# SensorNodeBoard_4_2_1AZ1b.net
KiCad netlist of a schematic drawn in EAGLE
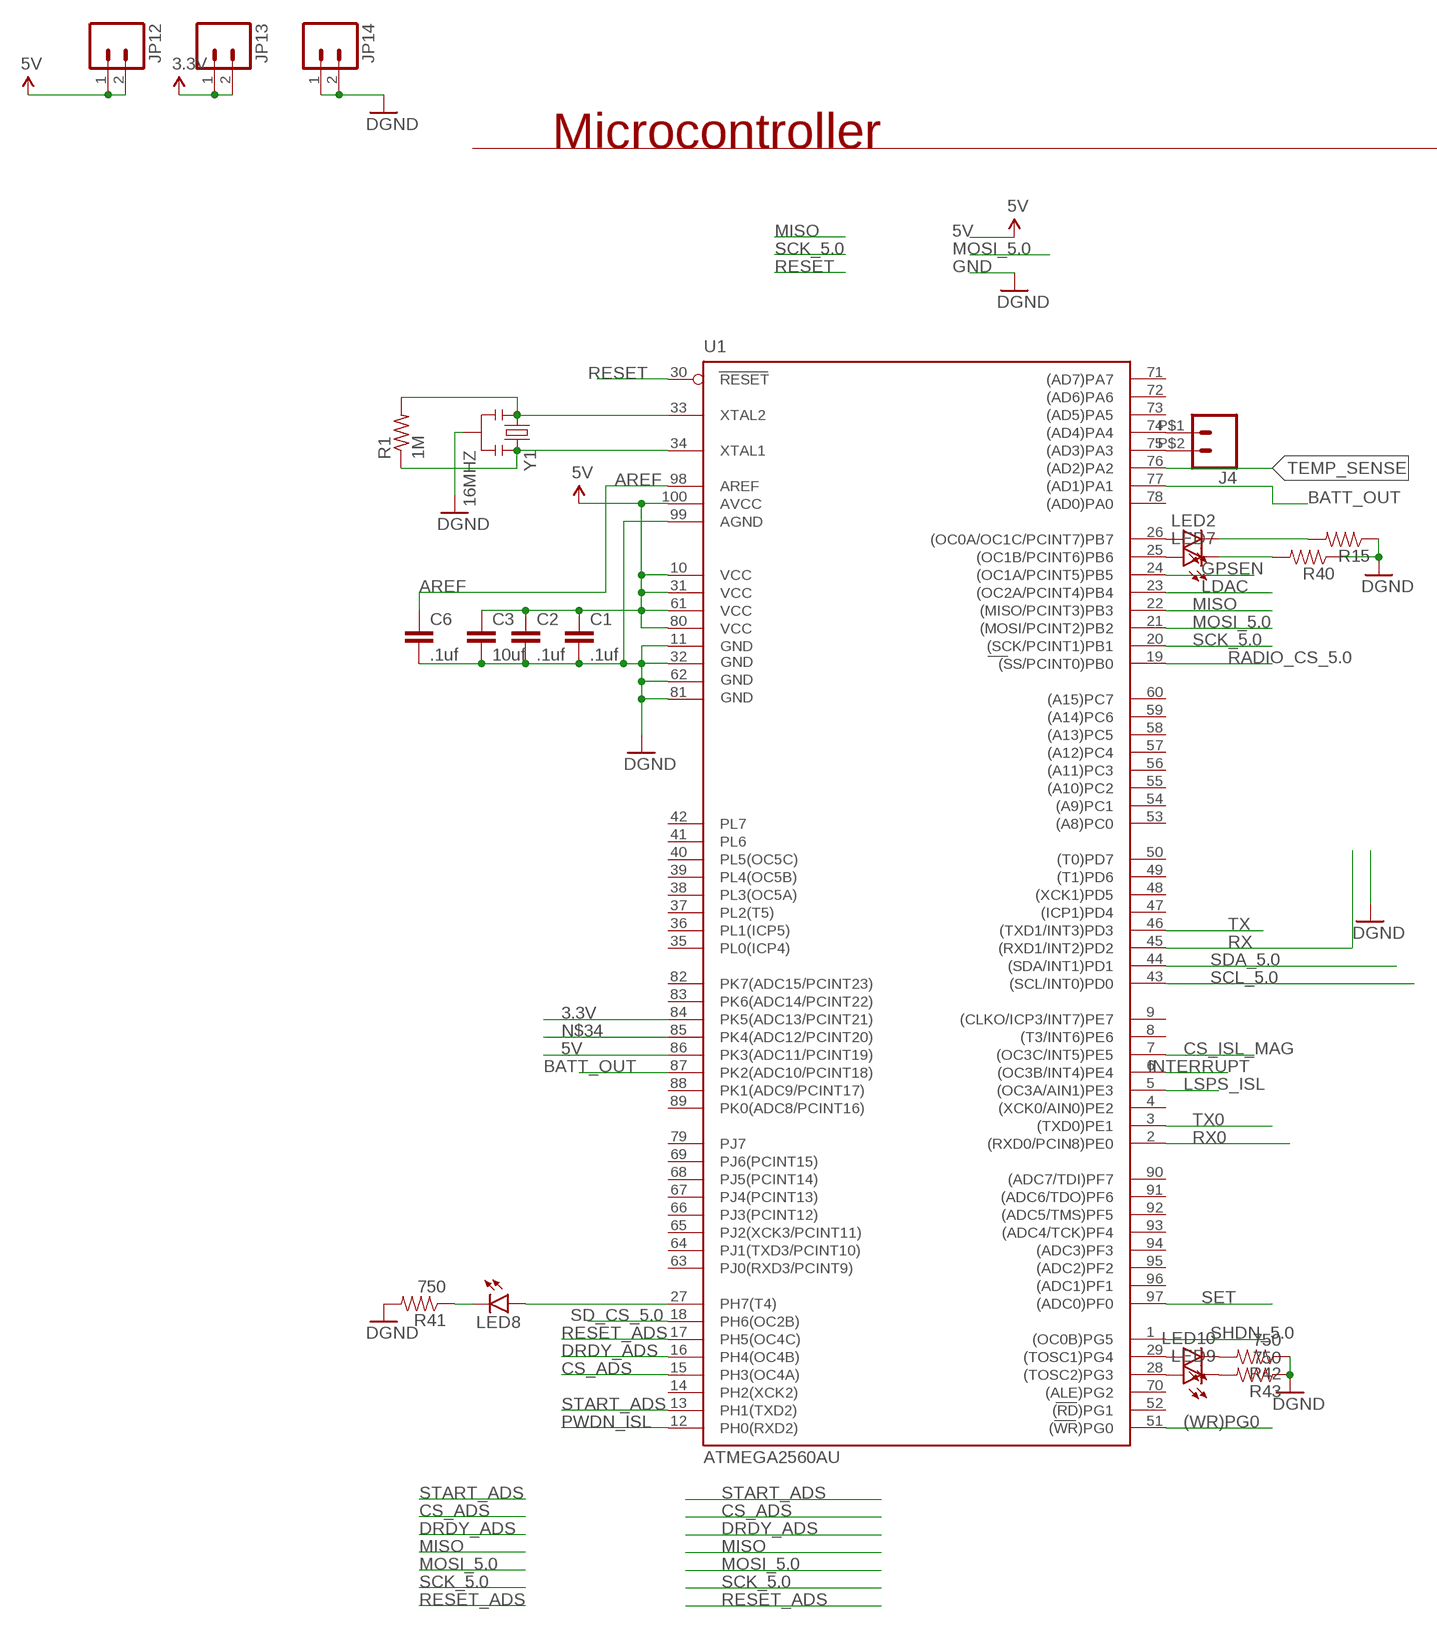
[diagram p0: schematic, sheet 1, part 1 of 2]
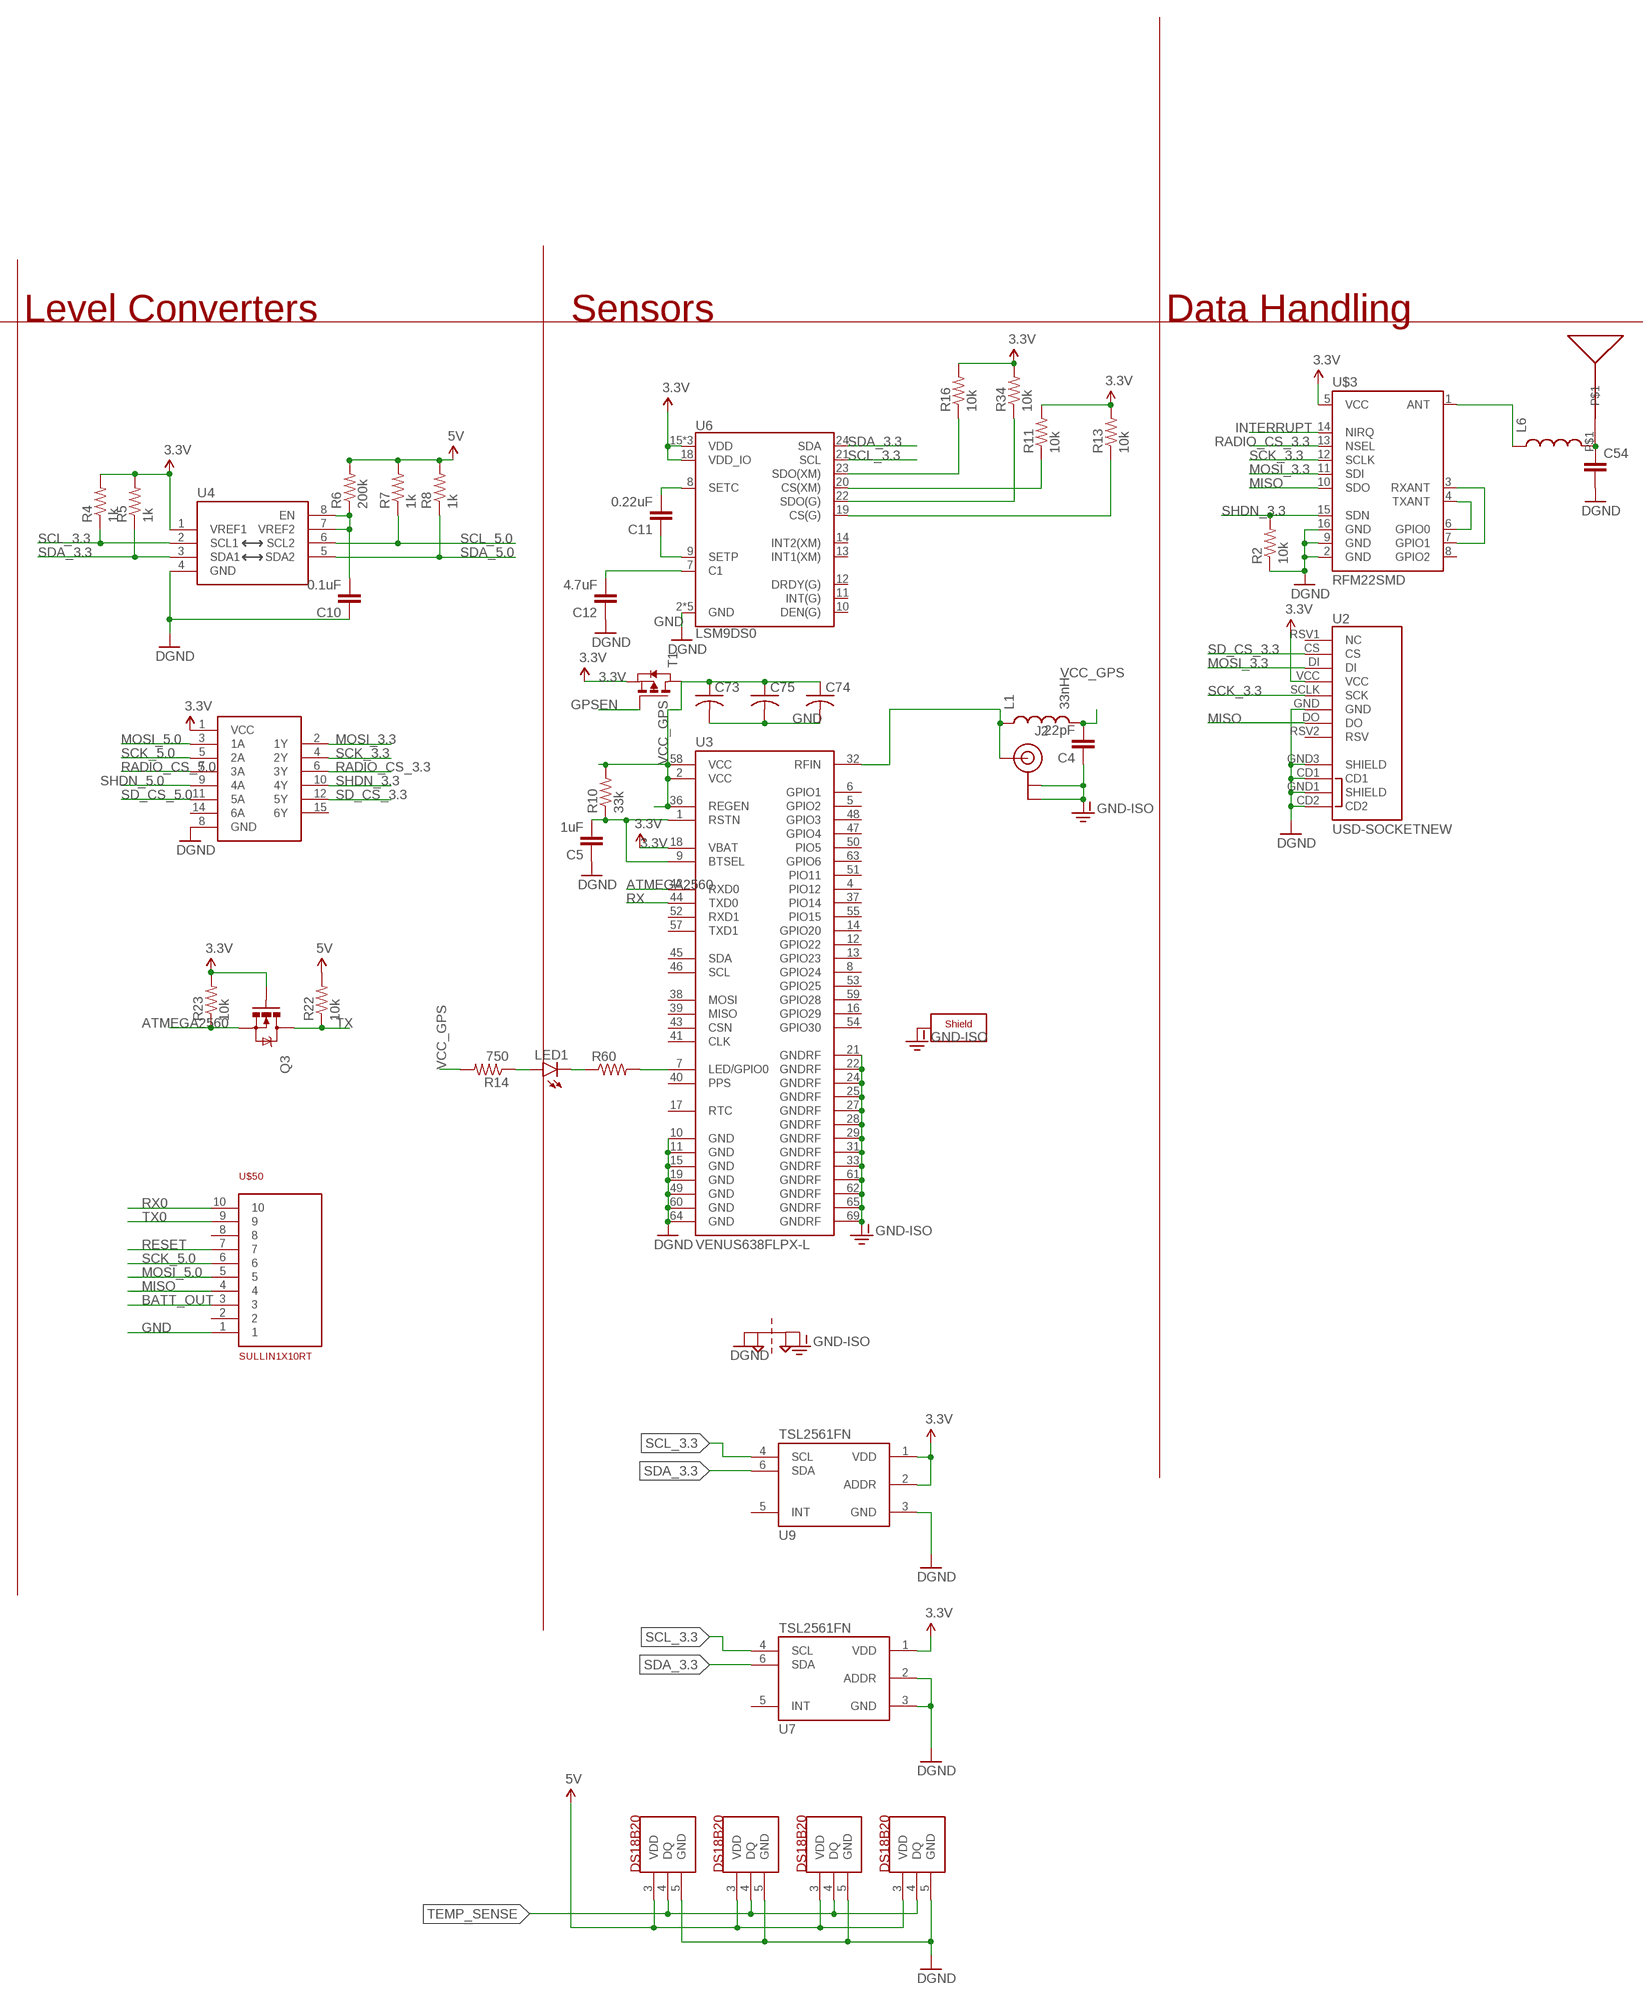
[diagram p1: schematic, sheet 1, part 2 of 2]
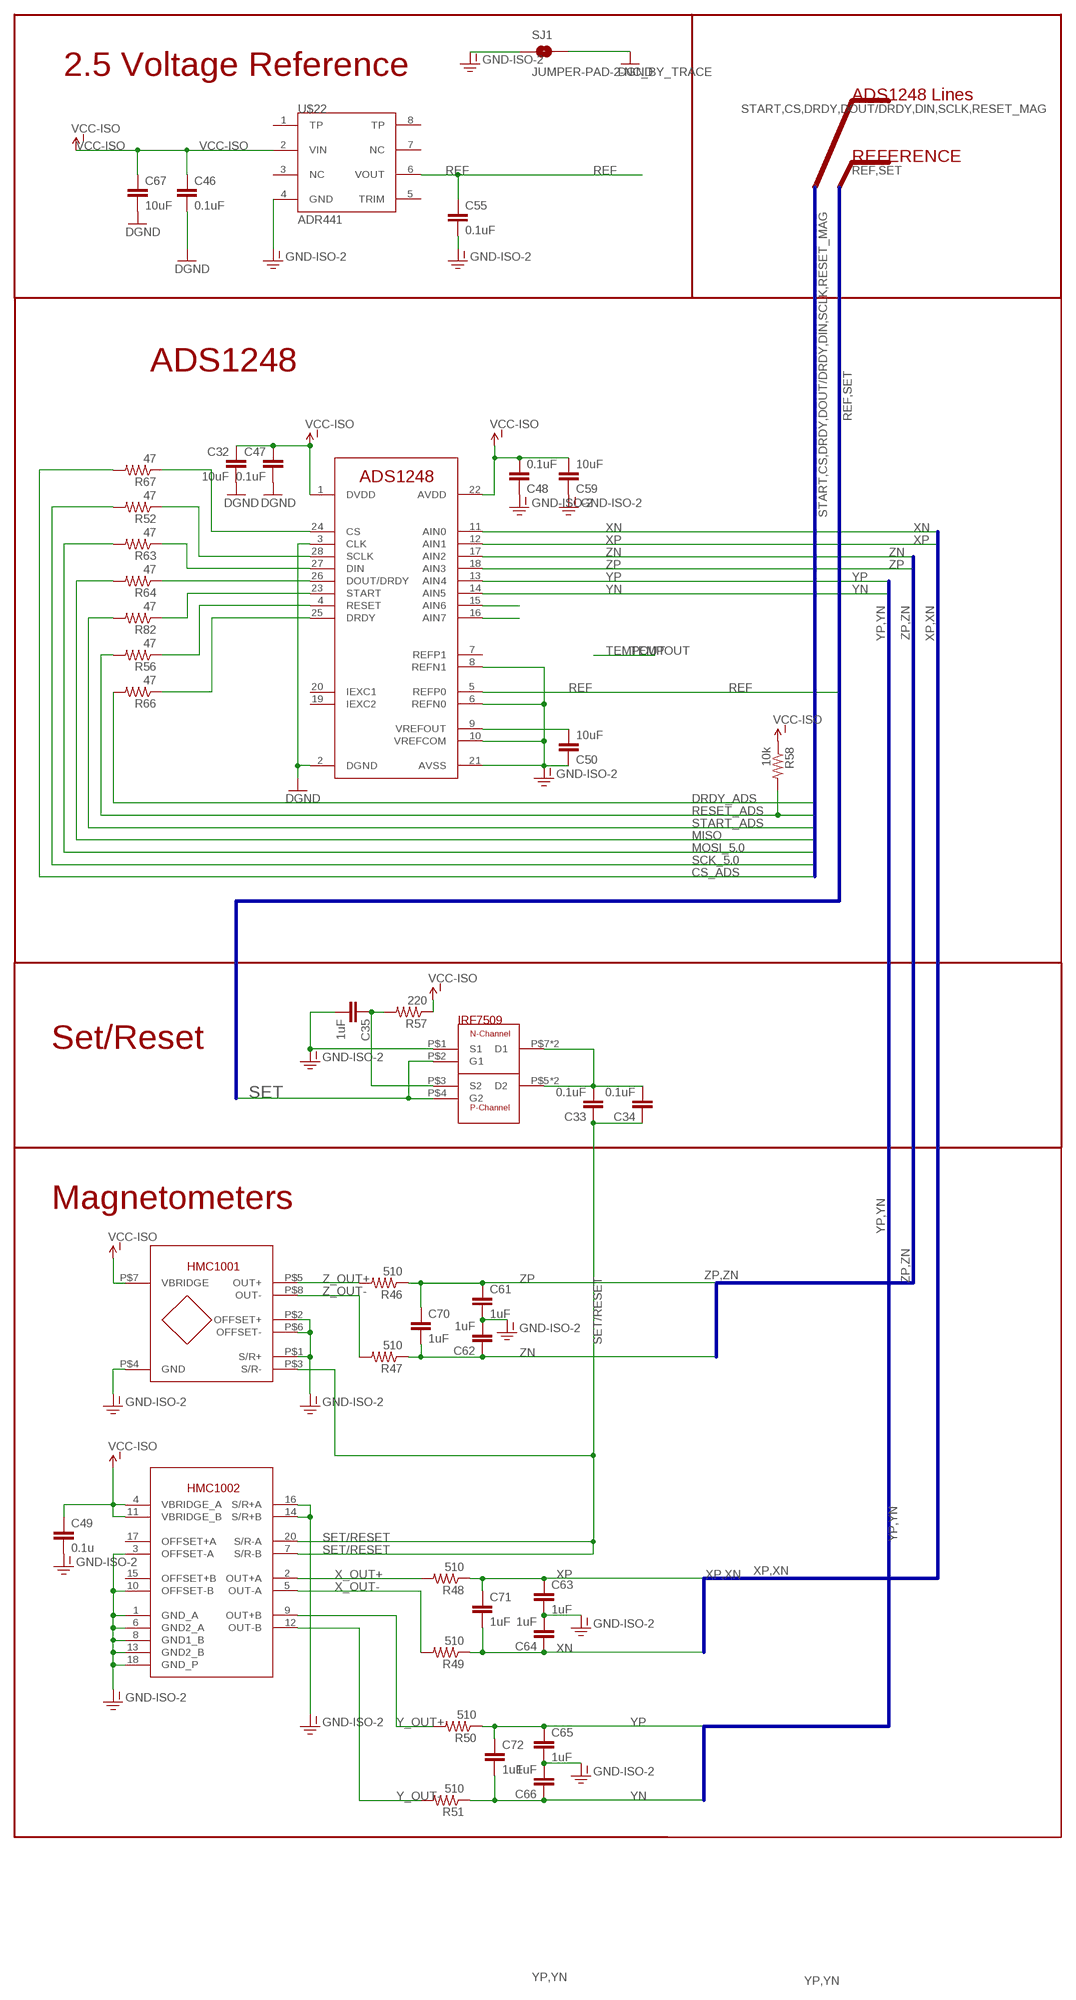
[diagram p2: schematic, sheet 2]
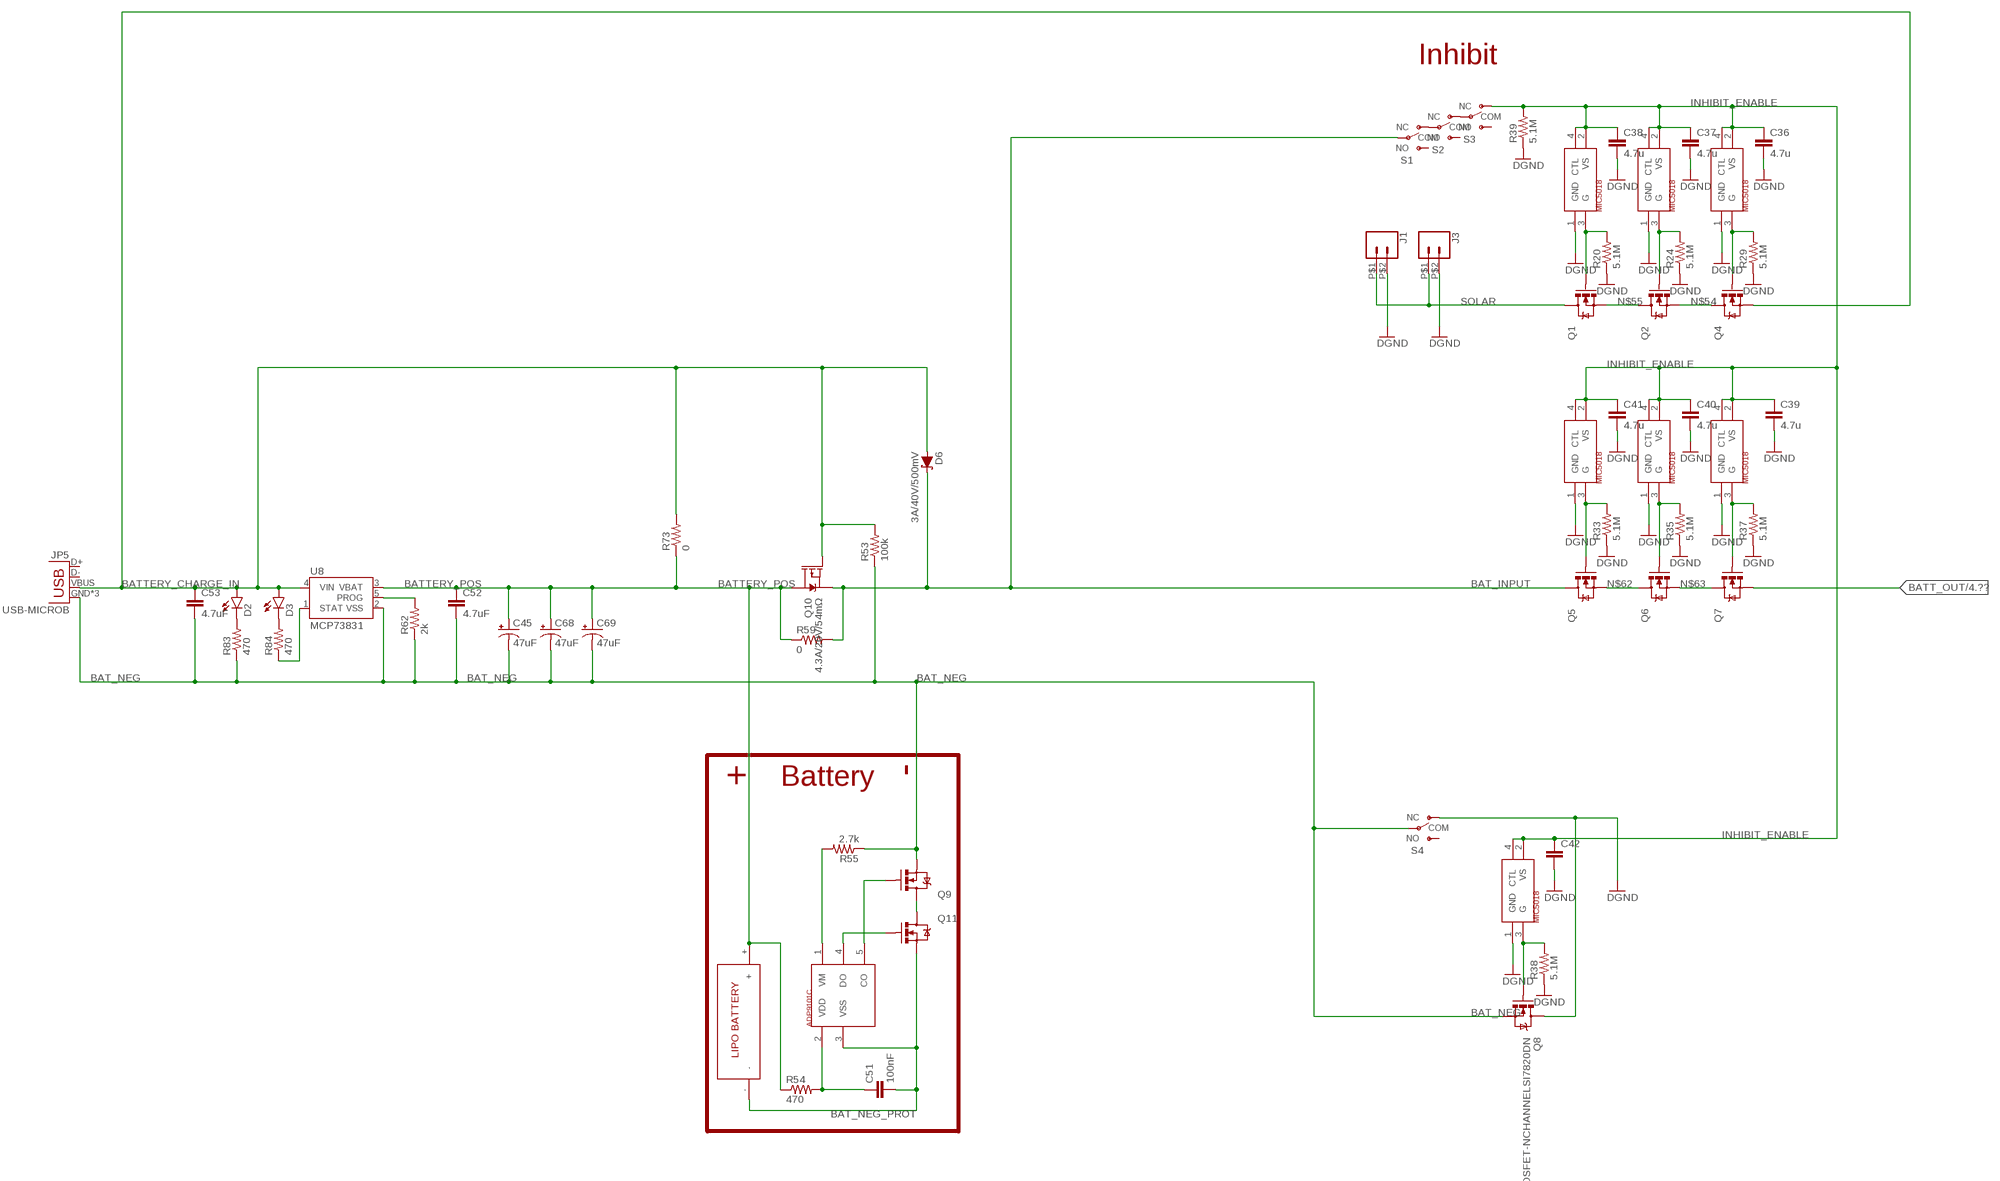
[diagram p3: schematic, sheet 3]
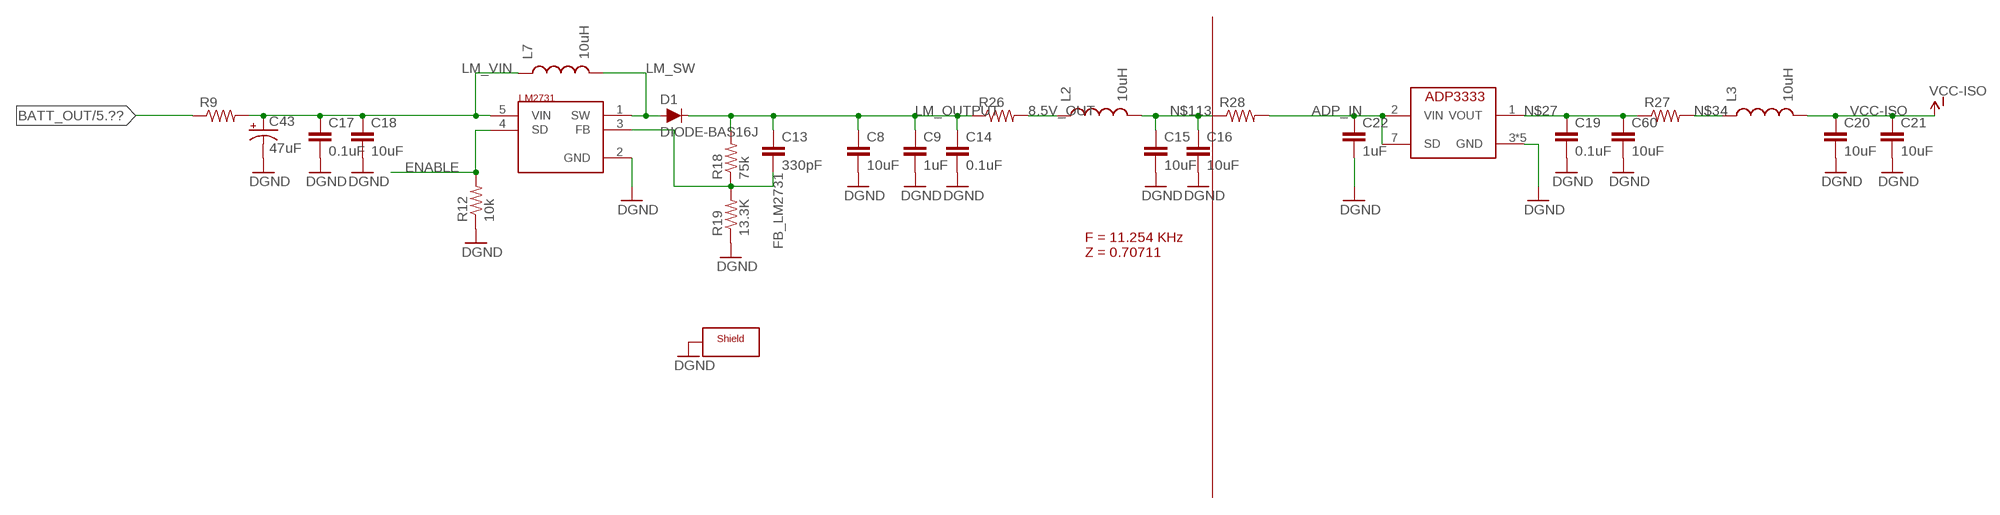
[diagram p4: schematic, sheet 4]
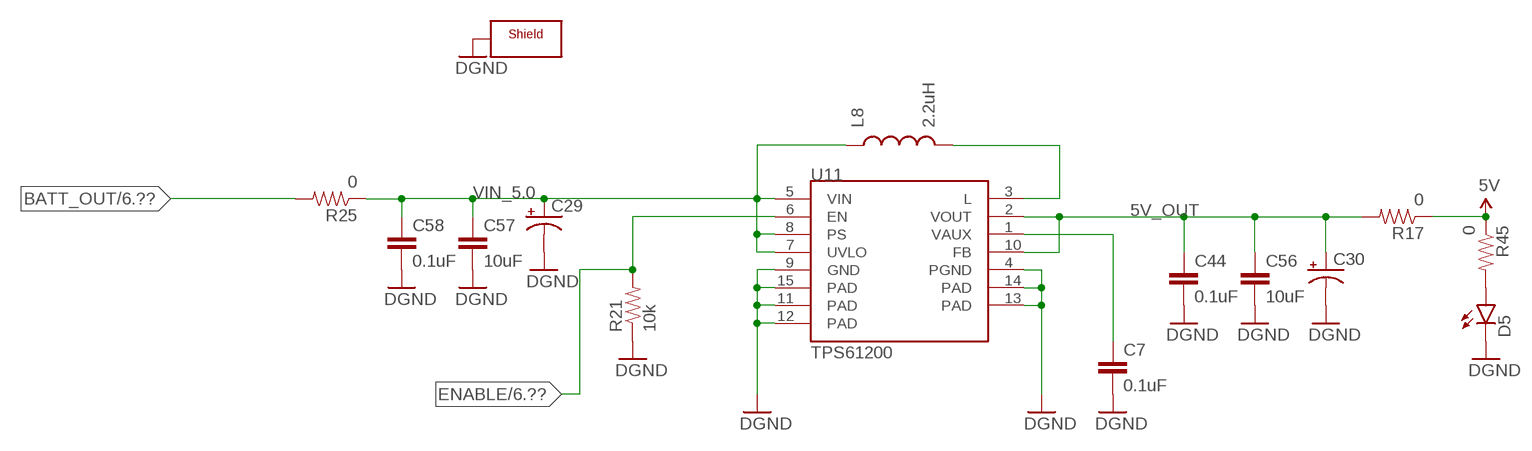
[diagram p5: schematic, sheet 5]
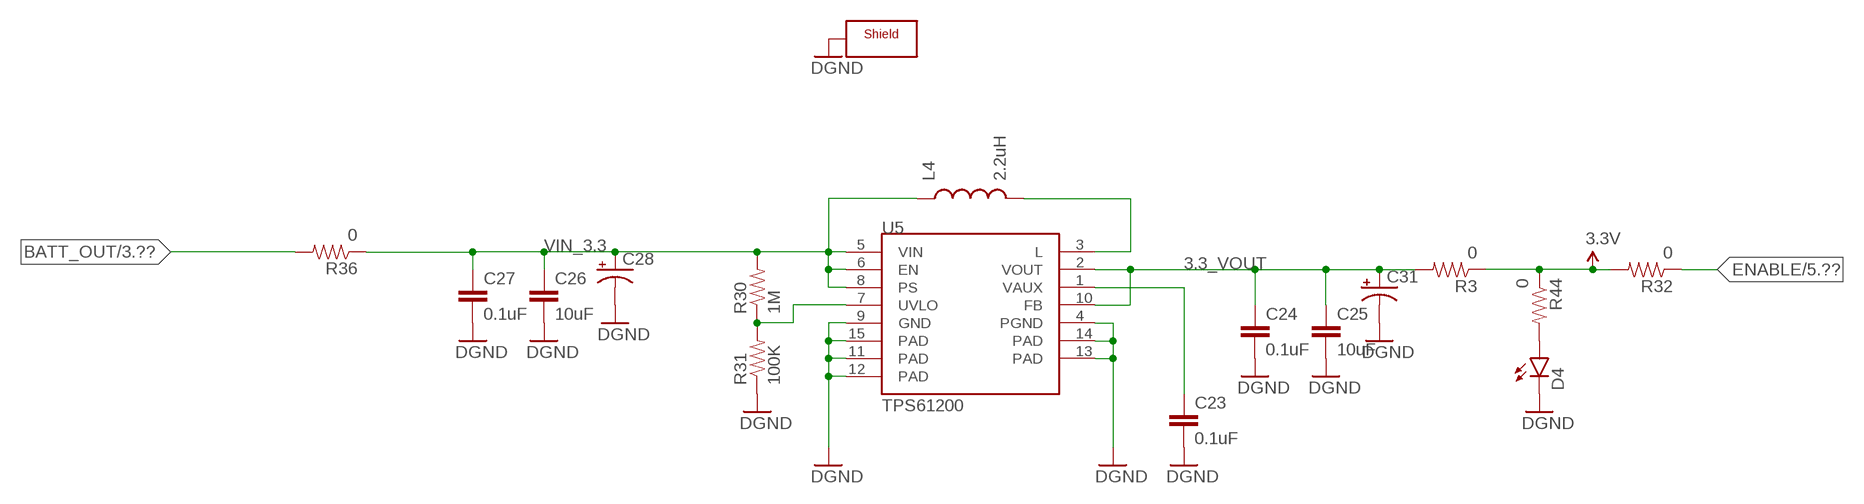
[diagram p6: schematic, sheet 6]

(export (version "E")
  (design (tool "Eeschema 10.0.6"))
  (components
    (comp (ref "C1")
      (value ".1uf")
      (footprint "eagle-import:0603-CAP")
      (libsource (lib "eagle-import") (part "SparkFun-Passives_CAP0603-CAP"))
    )
    (comp (ref "C2")
      (value ".1uf")
      (footprint "eagle-import:0603-CAP")
      (libsource (lib "eagle-import") (part "SparkFun-Passives_CAP0603-CAP"))
    )
    (comp (ref "C3")
      (value "10uf")
      (footprint "eagle-import:0603-CAP")
      (libsource (lib "eagle-import") (part "SparkFun-Passives_CAP0603-CAP"))
    )
    (comp (ref "C4")
      (value "22pF")
      (footprint "eagle-import:0603-CAP")
      (libsource (lib "eagle-import") (part "SparkFun-Passives_CAP0603-CAP"))
    )
    (comp (ref "C5")
      (value "1uF")
      (footprint "eagle-import:0603-CAP")
      (libsource (lib "eagle-import") (part "SparkFun-Passives_CAP0603-CAP"))
    )
    (comp (ref "C6")
      (value ".1uf")
      (footprint "eagle-import:0603-CAP")
      (libsource (lib "eagle-import") (part "SparkFun-Passives_CAP0603-CAP"))
    )
    (comp (ref "C10")
      (value "0.1uF")
      (footprint "eagle-import:0603-CAP")
      (libsource (lib "eagle-import") (part "SparkFun-Passives_CAP0603-CAP"))
    )
    (comp (ref "C11")
      (value "0.22uF")
      (footprint "eagle-import:0603-CAP")
      (libsource (lib "eagle-import") (part "SparkFun-Passives_CAP0603-CAP"))
    )
    (comp (ref "C12")
      (value "4.7uF")
      (footprint "eagle-import:0603-CAP")
      (libsource (lib "eagle-import") (part "SparkFun-Passives_CAP0603-CAP"))
    )
    (comp (ref "C54")
      (value "CAP0603-CAP")
      (footprint "eagle-import:0603-CAP")
      (libsource (lib "eagle-import") (part "SparkFun-Passives_CAP0603-CAP"))
    )
    (comp (ref "C73")
      (value "C-USC0603K")
      (footprint "eagle-import:C0603K")
      (libsource (lib "eagle-import") (part "C-USC0603K"))
    )
    (comp (ref "C74")
      (value "C-USC0603K")
      (footprint "eagle-import:C0603K")
      (libsource (lib "eagle-import") (part "C-USC0603K"))
    )
    (comp (ref "C75")
      (value "C-USC0603K")
      (footprint "eagle-import:C0603K")
      (libsource (lib "eagle-import") (part "C-USC0603K"))
    )
    (comp (ref "J2")
      (value "U.FL")
      (footprint "eagle-import:U.FL")
      (libsource (lib "eagle-import") (part "U.FL"))
    )
    (comp (ref "J4")
      (value "CONN_02HIROSE")
      (footprint "eagle-import:1X02_1.25")
      (libsource (lib "eagle-import") (part "CONN_02HIROSE"))
    )
    (comp (ref "JP12")
      (value "M02LOCK")
      (footprint "eagle-import:1X02_LOCK")
      (libsource (lib "eagle-import") (part "M02LOCK"))
    )
    (comp (ref "JP13")
      (value "M02LOCK")
      (footprint "eagle-import:1X02_LOCK")
      (libsource (lib "eagle-import") (part "M02LOCK"))
    )
    (comp (ref "JP14")
      (value "M02LOCK")
      (footprint "eagle-import:1X02_LOCK")
      (libsource (lib "eagle-import") (part "M02LOCK"))
    )
    (comp (ref "L1")
      (value "33nH")
      (footprint "eagle-import:0805")
      (libsource (lib "eagle-import") (part "INDUCTOR0805"))
    )
    (comp (ref "L6")
      (value "INDUCTOR0805")
      (footprint "eagle-import:0805")
      (libsource (lib "eagle-import") (part "INDUCTOR0805"))
    )
    (comp (ref "LED1")
      (value "LED0603")
      (footprint "eagle-import:LED-0603")
      (libsource (lib "eagle-import") (part "LED0603"))
    )
    (comp (ref "LED2")
      (value "LED0603")
      (footprint "eagle-import:LED-0603")
      (libsource (lib "eagle-import") (part "LED0603"))
    )
    (comp (ref "LED7")
      (value "LED0603")
      (footprint "eagle-import:LED-0603")
      (libsource (lib "eagle-import") (part "LED0603"))
    )
    (comp (ref "LED8")
      (value "LED0603")
      (footprint "eagle-import:LED-0603")
      (libsource (lib "eagle-import") (part "LED0603"))
    )
    (comp (ref "LED9")
      (value "LED0603")
      (footprint "eagle-import:LED-0603")
      (libsource (lib "eagle-import") (part "LED0603"))
    )
    (comp (ref "LED10")
      (value "LED0603")
      (footprint "eagle-import:LED-0603")
      (libsource (lib "eagle-import") (part "LED0603"))
    )
    (comp (ref "PT1")
      (value "2PT_GND_TIE")
      (footprint "eagle-import:2PT_GND_TIE")
      (libsource (lib "eagle-import") (part "2PT_GND_TIE"))
    )
    (comp (ref "Q3")
      (value "MOSFET-NCHANNEL2N7002PW")
      (footprint "eagle-import:SOT323")
      (libsource (lib "eagle-import") (part "MOSFET-NCHANNEL2N7002PW"))
    )
    (comp (ref "R1")
      (value "1M")
      (footprint "eagle-import:R1206")
      (libsource (lib "eagle-import") (part "R-US_R1206"))
    )
    (comp (ref "R2")
      (value "10k")
      (footprint "eagle-import:0603-RES")
      (libsource (lib "eagle-import") (part "RESISTOR0603-RES"))
    )
    (comp (ref "R4")
      (value "1k")
      (footprint "eagle-import:0603-RES")
      (libsource (lib "eagle-import") (part "RESISTOR0603-RES"))
    )
    (comp (ref "R5")
      (value "1k")
      (footprint "eagle-import:0603-RES")
      (libsource (lib "eagle-import") (part "RESISTOR0603-RES"))
    )
    (comp (ref "R6")
      (value "200k")
      (footprint "eagle-import:0603-RES")
      (libsource (lib "eagle-import") (part "RESISTOR0603-RES"))
    )
    (comp (ref "R7")
      (value "1k")
      (footprint "eagle-import:0603-RES")
      (libsource (lib "eagle-import") (part "RESISTOR0603-RES"))
    )
    (comp (ref "R8")
      (value "1k")
      (footprint "eagle-import:0603-RES")
      (libsource (lib "eagle-import") (part "RESISTOR0603-RES"))
    )
    (comp (ref "R10")
      (value "33k")
      (footprint "eagle-import:0603-RES")
      (libsource (lib "eagle-import") (part "RESISTOR0603-RES"))
    )
    (comp (ref "R11")
      (value "10k")
      (footprint "eagle-import:0603-RES")
      (libsource (lib "eagle-import") (part "RESISTOR0603-RES"))
    )
    (comp (ref "R13")
      (value "10k")
      (footprint "eagle-import:0603-RES")
      (libsource (lib "eagle-import") (part "RESISTOR0603-RES"))
    )
    (comp (ref "R14")
      (value "750")
      (footprint "eagle-import:0603-RES")
      (libsource (lib "eagle-import") (part "RESISTOR0603-RES"))
    )
    (comp (ref "R15")
      (value "RESISTOR0603-RES")
      (footprint "eagle-import:0603-RES")
      (libsource (lib "eagle-import") (part "RESISTOR0603-RES"))
    )
    (comp (ref "R16")
      (value "10k")
      (footprint "eagle-import:0603-RES")
      (libsource (lib "eagle-import") (part "RESISTOR0603-RES"))
    )
    (comp (ref "R22")
      (value "10k")
      (footprint "eagle-import:0603-RES")
      (libsource (lib "eagle-import") (part "RESISTOR0603-RES"))
    )
    (comp (ref "R23")
      (value "10k")
      (footprint "eagle-import:0603-RES")
      (libsource (lib "eagle-import") (part "RESISTOR0603-RES"))
    )
    (comp (ref "R34")
      (value "10k")
      (footprint "eagle-import:0603-RES")
      (libsource (lib "eagle-import") (part "RESISTOR0603-RES"))
    )
    (comp (ref "R40")
      (value "RESISTOR0603-RES")
      (footprint "eagle-import:0603-RES")
      (libsource (lib "eagle-import") (part "RESISTOR0603-RES"))
    )
    (comp (ref "R41")
      (value "750")
      (footprint "eagle-import:0603-RES")
      (libsource (lib "eagle-import") (part "RESISTOR0603-RES"))
    )
    (comp (ref "R42")
      (value "750")
      (footprint "eagle-import:0603-RES")
      (libsource (lib "eagle-import") (part "RESISTOR0603-RES"))
    )
    (comp (ref "R43")
      (value "750")
      (footprint "eagle-import:0603-RES")
      (libsource (lib "eagle-import") (part "RESISTOR0603-RES"))
    )
    (comp (ref "R60")
      (value "R-US_R0603")
      (footprint "eagle-import:R0603")
      (libsource (lib "eagle-import") (part "R-US_R0603"))
    )
    (comp (ref "T1")
      (value "PMOSSOT23-6")
      (footprint "eagle-import:SOT23-6")
      (libsource (lib "eagle-import") (part "PMOSSOT23-6"))
    )
    (comp (ref "U$1")
      (value "74HC4050")
      (footprint "eagle-import:TSSOP16")
      (libsource (lib "eagle-import") (part "74HC4050"))
    )
    (comp (ref "U$3")
      (value "RFM22SMD")
      (footprint "eagle-import:RFM22-XXX-S2")
      (libsource (lib "eagle-import") (part "RFM22SMD"))
    )
    (comp (ref "U$23")
      (value "SNB_ANT")
      (footprint "eagle-import:SLOT")
      (libsource (lib "eagle-import") (part "SNB_ANT"))
    )
    (comp (ref "U$24")
      (value "DS18B202")
      (footprint "eagle-import:SO08")
      (libsource (lib "eagle-import") (part "DS18B202"))
    )
    (comp (ref "U$25")
      (value "DS18B202")
      (footprint "eagle-import:SO08")
      (libsource (lib "eagle-import") (part "DS18B202"))
    )
    (comp (ref "U$47")
      (value "DS18B202")
      (footprint "eagle-import:SO08")
      (libsource (lib "eagle-import") (part "DS18B202"))
    )
    (comp (ref "U$48")
      (value "DS18B202")
      (footprint "eagle-import:SO08")
      (libsource (lib "eagle-import") (part "DS18B202"))
    )
    (comp (ref "U$50")
      (value "SULLIN1X10RT")
      (footprint "eagle-import:SULLRT1X10-2MM")
      (libsource (lib "eagle-import") (part "SULLIN1X10RT"))
    )
    (comp (ref "U$52")
      (value "SHEILD3")
      (footprint "eagle-import:SHIELD_BMI-201-C-REV")
      (libsource (lib "eagle-import") (part "SHEILD3"))
    )
    (comp (ref "U1")
      (value "ATMEGA2560AU")
      (footprint "eagle-import:TQFP100")
      (libsource (lib "eagle-import") (part "ATMEGA2560AU"))
    )
    (comp (ref "U2")
      (value "USD-SOCKETNEW")
      (footprint "eagle-import:MICRO-SD-SOCKET-PP")
      (libsource (lib "eagle-import") (part "USD-SOCKETNEW"))
    )
    (comp (ref "U3")
      (value "VENUS638FLPX-L")
      (footprint "eagle-import:VENUS638FLPX")
      (libsource (lib "eagle-import") (part "VENUS638FLPX-L"))
    )
    (comp (ref "U4")
      (value "PCA9306")
      (footprint "eagle-import:PSOP-8")
      (libsource (lib "eagle-import") (part "PCA9306"))
    )
    (comp (ref "U6")
      (value "LSM9DS0")
      (footprint "eagle-import:LGA-24")
      (libsource (lib "eagle-import") (part "LSM9DS0"))
    )
    (comp (ref "U7")
      (value "TSL2561FN")
      (footprint "eagle-import:FN-6")
      (libsource (lib "eagle-import") (part "TSL2561FN"))
    )
    (comp (ref "U9")
      (value "TSL2561FN")
      (footprint "eagle-import:FN-6")
      (libsource (lib "eagle-import") (part "TSL2561FN"))
    )
    (comp (ref "Y1")
      (value "16MHZ")
      (footprint "eagle-import:RESONATOR-SMD")
      (libsource (lib "eagle-import") (part "RESONATOR16MHZ"))
    )
    (comp (ref "C23")
      (value "0.1uF")
      (footprint "eagle-import:0603-CAP")
      (libsource (lib "eagle-import") (part "SparkFun-Passives_CAP0603-CAP"))
    )
    (comp (ref "C24")
      (value "0.1uF")
      (footprint "eagle-import:0603-CAP")
      (libsource (lib "eagle-import") (part "SparkFun-Passives_CAP0603-CAP"))
    )
    (comp (ref "C25")
      (value "10uF")
      (footprint "eagle-import:0603-CAP")
      (libsource (lib "eagle-import") (part "SparkFun-Passives_CAP0603-CAP"))
    )
    (comp (ref "C26")
      (value "10uF")
      (footprint "eagle-import:0603-CAP")
      (libsource (lib "eagle-import") (part "SparkFun-Passives_CAP0603-CAP"))
    )
    (comp (ref "C27")
      (value "0.1uF")
      (footprint "eagle-import:0603-CAP")
      (libsource (lib "eagle-import") (part "SparkFun-Passives_CAP0603-CAP"))
    )
    (comp (ref "C28")
      (value "CAP_POL1206")
      (footprint "eagle-import:EIA3216")
      (libsource (lib "eagle-import") (part "CAP_POL1206"))
    )
    (comp (ref "C31")
      (value "CAP_POL1206")
      (footprint "eagle-import:EIA3216")
      (libsource (lib "eagle-import") (part "CAP_POL1206"))
    )
    (comp (ref "D4")
      (value "LED0603")
      (footprint "eagle-import:LED-0603")
      (libsource (lib "eagle-import") (part "LED0603"))
    )
    (comp (ref "L4")
      (value "2.2uH")
      (footprint "eagle-import:1210")
      (libsource (lib "eagle-import") (part "INDUCTOR1210"))
    )
    (comp (ref "R3")
      (value "0")
      (footprint "eagle-import:1206")
      (libsource (lib "eagle-import") (part "RESISTOR1206"))
    )
    (comp (ref "R30")
      (value "1M")
      (footprint "eagle-import:0603-RES")
      (libsource (lib "eagle-import") (part "RESISTOR0603-RES"))
    )
    (comp (ref "R31")
      (value "100K")
      (footprint "eagle-import:0603-RES")
      (libsource (lib "eagle-import") (part "RESISTOR0603-RES"))
    )
    (comp (ref "R32")
      (value "0")
      (footprint "eagle-import:0603-RES")
      (libsource (lib "eagle-import") (part "RESISTOR0603-RES"))
    )
    (comp (ref "R36")
      (value "0")
      (footprint "eagle-import:1206")
      (libsource (lib "eagle-import") (part "RESISTOR1206"))
    )
    (comp (ref "R44")
      (value "0")
      (footprint "eagle-import:0603-RES")
      (libsource (lib "eagle-import") (part "RESISTOR0603-RES"))
    )
    (comp (ref "U$41")
      (value "SHEILD")
      (footprint "eagle-import:SHIELD_BMI-S-201-C")
      (libsource (lib "eagle-import") (part "SHEILD"))
    )
    (comp (ref "U5")
      (value "TPS61200")
      (footprint "eagle-import:QFN-10_PAD")
      (libsource (lib "eagle-import") (part "TPS61200"))
    )
    (comp (ref "C7")
      (value "0.1uF")
      (footprint "eagle-import:0603-CAP")
      (libsource (lib "eagle-import") (part "SparkFun-Passives_CAP0603-CAP"))
    )
    (comp (ref "C29")
      (value "CAP_POL1206")
      (footprint "eagle-import:EIA3216")
      (libsource (lib "eagle-import") (part "CAP_POL1206"))
    )
    (comp (ref "C30")
      (value "CAP_POL1206")
      (footprint "eagle-import:EIA3216")
      (libsource (lib "eagle-import") (part "CAP_POL1206"))
    )
    (comp (ref "C44")
      (value "0.1uF")
      (footprint "eagle-import:0603-CAP")
      (libsource (lib "eagle-import") (part "SparkFun-Passives_CAP0603-CAP"))
    )
    (comp (ref "C56")
      (value "10uF")
      (footprint "eagle-import:0603-CAP")
      (libsource (lib "eagle-import") (part "SparkFun-Passives_CAP0603-CAP"))
    )
    (comp (ref "C57")
      (value "10uF")
      (footprint "eagle-import:0603-CAP")
      (libsource (lib "eagle-import") (part "SparkFun-Passives_CAP0603-CAP"))
    )
    (comp (ref "C58")
      (value "0.1uF")
      (footprint "eagle-import:0603-CAP")
      (libsource (lib "eagle-import") (part "SparkFun-Passives_CAP0603-CAP"))
    )
    (comp (ref "D5")
      (value "LED0603")
      (footprint "eagle-import:LED-0603")
      (libsource (lib "eagle-import") (part "LED0603"))
    )
    (comp (ref "L8")
      (value "2.2uH")
      (footprint "eagle-import:1210")
      (libsource (lib "eagle-import") (part "INDUCTOR1210"))
    )
    (comp (ref "R17")
      (value "0")
      (footprint "eagle-import:1206")
      (libsource (lib "eagle-import") (part "RESISTOR1206"))
    )
    (comp (ref "R21")
      (value "10k")
      (footprint "eagle-import:0603-RES")
      (libsource (lib "eagle-import") (part "RESISTOR0603-RES"))
    )
    (comp (ref "R25")
      (value "0")
      (footprint "eagle-import:1206")
      (libsource (lib "eagle-import") (part "RESISTOR1206"))
    )
    (comp (ref "R45")
      (value "0")
      (footprint "eagle-import:0603-RES")
      (libsource (lib "eagle-import") (part "RESISTOR0603-RES"))
    )
    (comp (ref "U$39")
      (value "SHEILD")
      (footprint "eagle-import:SHIELD_BMI-S-201-C")
      (libsource (lib "eagle-import") (part "SHEILD"))
    )
    (comp (ref "U11")
      (value "TPS61200")
      (footprint "eagle-import:QFN-10_PAD")
      (libsource (lib "eagle-import") (part "TPS61200"))
    )
    (comp (ref "C36")
      (value "4.7u")
      (footprint "eagle-import:0603-CAP")
      (libsource (lib "eagle-import") (part "CAP0603-CAP"))
    )
    (comp (ref "C37")
      (value "4.7u")
      (footprint "eagle-import:0603-CAP")
      (libsource (lib "eagle-import") (part "CAP0603-CAP"))
    )
    (comp (ref "C38")
      (value "4.7u")
      (footprint "eagle-import:0603-CAP")
      (libsource (lib "eagle-import") (part "CAP0603-CAP"))
    )
    (comp (ref "C39")
      (value "4.7u")
      (footprint "eagle-import:0603-CAP")
      (libsource (lib "eagle-import") (part "CAP0603-CAP"))
    )
    (comp (ref "C40")
      (value "4.7u")
      (footprint "eagle-import:0603-CAP")
      (libsource (lib "eagle-import") (part "CAP0603-CAP"))
    )
    (comp (ref "C41")
      (value "4.7u")
      (footprint "eagle-import:0603-CAP")
      (libsource (lib "eagle-import") (part "CAP0603-CAP"))
    )
    (comp (ref "C42")
      (value "CAP0603-CAP")
      (footprint "eagle-import:0603-CAP")
      (libsource (lib "eagle-import") (part "CAP0603-CAP"))
    )
    (comp (ref "C45")
      (value "47uF")
      (footprint "eagle-import:EIA3216")
      (libsource (lib "eagle-import") (part "CAP_POL1206"))
    )
    (comp (ref "C51")
      (value "100nF")
      (footprint "eagle-import:0603-CAP")
      (libsource (lib "eagle-import") (part "SparkFun-Passives_CAP0603-CAP"))
    )
    (comp (ref "C52")
      (value "4.7uF")
      (footprint "eagle-import:0603-CAP")
      (libsource (lib "eagle-import") (part "SparkFun-Passives_CAP0603-CAP"))
    )
    (comp (ref "C53")
      (value "4.7uF")
      (footprint "eagle-import:0603-CAP")
      (libsource (lib "eagle-import") (part "SparkFun-Passives_CAP0603-CAP"))
    )
    (comp (ref "C68")
      (value "47uF")
      (footprint "eagle-import:EIA3216")
      (libsource (lib "eagle-import") (part "CAP_POL1206"))
    )
    (comp (ref "C69")
      (value "47uF")
      (footprint "eagle-import:EIA3216")
      (libsource (lib "eagle-import") (part "CAP_POL1206"))
    )
    (comp (ref "D2")
      (value "LED0603")
      (footprint "eagle-import:LED-0603")
      (libsource (lib "eagle-import") (part "LED0603"))
    )
    (comp (ref "D3")
      (value "LED0603")
      (footprint "eagle-import:LED-0603")
      (libsource (lib "eagle-import") (part "LED0603"))
    )
    (comp (ref "D6")
      (value "3A/40V/500mV")
      (footprint "eagle-import:SMA-DIODE")
      (libsource (lib "eagle-import") (part "DIODE-SCHOTTKY-B340A"))
    )
    (comp (ref "J1")
      (value "CONN_02HIROSE")
      (footprint "eagle-import:1X02_1.25")
      (libsource (lib "eagle-import") (part "CONN_02HIROSE"))
    )
    (comp (ref "J3")
      (value "CONN_02HIROSE")
      (footprint "eagle-import:1X02_1.25")
      (libsource (lib "eagle-import") (part "CONN_02HIROSE"))
    )
    (comp (ref "JP5")
      (value "USB-MICROB")
      (footprint "eagle-import:USB-MICROB")
      (libsource (lib "eagle-import") (part "USB-MICROB"))
    )
    (comp (ref "Q1")
      (value "MOSFET-NCHANNELSI7820DN")
      (footprint "eagle-import:POWERPAK1212-8")
      (libsource (lib "eagle-import") (part "MOSFET-NCHANNELSI7820DN"))
    )
    (comp (ref "Q2")
      (value "MOSFET-NCHANNELSI7820DN")
      (footprint "eagle-import:POWERPAK1212-8")
      (libsource (lib "eagle-import") (part "MOSFET-NCHANNELSI7820DN"))
    )
    (comp (ref "Q4")
      (value "MOSFET-NCHANNELSI7820DN")
      (footprint "eagle-import:POWERPAK1212-8")
      (libsource (lib "eagle-import") (part "MOSFET-NCHANNELSI7820DN"))
    )
    (comp (ref "Q5")
      (value "MOSFET-NCHANNELSI7820DN")
      (footprint "eagle-import:POWERPAK1212-8")
      (libsource (lib "eagle-import") (part "MOSFET-NCHANNELSI7820DN"))
    )
    (comp (ref "Q6")
      (value "MOSFET-NCHANNELSI7820DN")
      (footprint "eagle-import:POWERPAK1212-8")
      (libsource (lib "eagle-import") (part "MOSFET-NCHANNELSI7820DN"))
    )
    (comp (ref "Q7")
      (value "MOSFET-NCHANNELSI7820DN")
      (footprint "eagle-import:POWERPAK1212-8")
      (libsource (lib "eagle-import") (part "MOSFET-NCHANNELSI7820DN"))
    )
    (comp (ref "Q8")
      (value "MOSFET-NCHANNELSI7820DN")
      (footprint "eagle-import:POWERPAK1212-8")
      (libsource (lib "eagle-import") (part "MOSFET-NCHANNELSI7820DN"))
    )
    (comp (ref "Q9")
      (value "MOSFET-NCHANNELSSM3K324R")
      (footprint "eagle-import:SOT23-3@1")
      (libsource (lib "eagle-import") (part "MOSFET-NCHANNELSSM3K324R"))
    )
    (comp (ref "Q10")
      (value "4.3A/20V/54mΩ")
      (footprint "eagle-import:SOT23-3")
      (libsource (lib "eagle-import") (part "MOSFET_PCH-IRLML2244"))
    )
    (comp (ref "Q11")
      (value "MOSFET-NCHANNELSSM3K324R")
      (footprint "eagle-import:SOT23-3@1")
      (libsource (lib "eagle-import") (part "MOSFET-NCHANNELSSM3K324R"))
    )
    (comp (ref "R20")
      (value "5.1M")
      (footprint "eagle-import:0603-RES")
      (libsource (lib "eagle-import") (part "RESISTOR0603-RES"))
    )
    (comp (ref "R24")
      (value "5.1M")
      (footprint "eagle-import:0603-RES")
      (libsource (lib "eagle-import") (part "RESISTOR0603-RES"))
    )
    (comp (ref "R29")
      (value "5.1M")
      (footprint "eagle-import:0603-RES")
      (libsource (lib "eagle-import") (part "RESISTOR0603-RES"))
    )
    (comp (ref "R33")
      (value "5.1M")
      (footprint "eagle-import:0603-RES")
      (libsource (lib "eagle-import") (part "RESISTOR0603-RES"))
    )
    (comp (ref "R35")
      (value "5.1M")
      (footprint "eagle-import:0603-RES")
      (libsource (lib "eagle-import") (part "RESISTOR0603-RES"))
    )
    (comp (ref "R37")
      (value "5.1M")
      (footprint "eagle-import:0603-RES")
      (libsource (lib "eagle-import") (part "RESISTOR0603-RES"))
    )
    (comp (ref "R38")
      (value "5.1M")
      (footprint "eagle-import:0603-RES")
      (libsource (lib "eagle-import") (part "RESISTOR0603-RES"))
    )
    (comp (ref "R39")
      (value "5.1M")
      (footprint "eagle-import:0603-RES")
      (libsource (lib "eagle-import") (part "RESISTOR0603-RES"))
    )
    (comp (ref "R53")
      (value "100k")
      (footprint "eagle-import:0603-RES")
      (libsource (lib "eagle-import") (part "RESISTOR0603-RES"))
    )
    (comp (ref "R54")
      (value "470")
      (footprint "eagle-import:0603-RES")
      (libsource (lib "eagle-import") (part "RESISTOR0603-RES"))
    )
    (comp (ref "R55")
      (value "2.7k")
      (footprint "eagle-import:0603-RES")
      (libsource (lib "eagle-import") (part "RESISTOR0603-RES"))
    )
    (comp (ref "R59")
      (value "0")
      (footprint "eagle-import:R2010")
      (libsource (lib "eagle-import") (part "RESISTOR2010"))
    )
    (comp (ref "R62")
      (value "2k")
      (footprint "eagle-import:R0603")
      (libsource (lib "eagle-import") (part "R-US_R0603"))
    )
    (comp (ref "R73")
      (value "0")
      (footprint "eagle-import:R2010")
      (libsource (lib "eagle-import") (part "RESISTOR2010"))
    )
    (comp (ref "R83")
      (value "470")
      (footprint "eagle-import:0603-RES")
      (libsource (lib "eagle-import") (part "RESISTOR0603-RES"))
    )
    (comp (ref "R84")
      (value "470")
      (footprint "eagle-import:0603-RES")
      (libsource (lib "eagle-import") (part "RESISTOR0603-RES"))
    )
    (comp (ref "S1")
      (value "SWITCH-SPDT")
      (footprint "eagle-import:CHERRY_SWITCH")
      (libsource (lib "eagle-import") (part "SWITCH-SPDT"))
    )
    (comp (ref "S2")
      (value "SWITCH-SPDT")
      (footprint "eagle-import:CHERRY_SWITCH")
      (libsource (lib "eagle-import") (part "SWITCH-SPDT"))
    )
    (comp (ref "S3")
      (value "SWITCH-SPDT")
      (footprint "eagle-import:CHERRY_SWITCH")
      (libsource (lib "eagle-import") (part "SWITCH-SPDT"))
    )
    (comp (ref "S4")
      (value "SWITCH-SPDT")
      (footprint "eagle-import:CHERRY_SWITCH")
      (libsource (lib "eagle-import") (part "SWITCH-SPDT"))
    )
    (comp (ref "U$8")
      (value "MIC5018")
      (footprint "eagle-import:SOT143")
      (libsource (lib "eagle-import") (part "MIC5018"))
    )
    (comp (ref "U$13")
      (value "MIC5018")
      (footprint "eagle-import:SOT143")
      (libsource (lib "eagle-import") (part "MIC5018"))
    )
    (comp (ref "U$14")
      (value "MIC5018")
      (footprint "eagle-import:SOT143")
      (libsource (lib "eagle-import") (part "MIC5018"))
    )
    (comp (ref "U$15")
      (value "MIC5018")
      (footprint "eagle-import:SOT143")
      (libsource (lib "eagle-import") (part "MIC5018"))
    )
    (comp (ref "U$16")
      (value "MIC5018")
      (footprint "eagle-import:SOT143")
      (libsource (lib "eagle-import") (part "MIC5018"))
    )
    (comp (ref "U$18")
      (value "BATTERY")
      (footprint "eagle-import:BATTERY")
      (libsource (lib "eagle-import") (part "BATTERY"))
    )
    (comp (ref "U$19")
      (value "MIC5018")
      (footprint "eagle-import:SOT143")
      (libsource (lib "eagle-import") (part "MIC5018"))
    )
    (comp (ref "U$20")
      (value "MIC5018")
      (footprint "eagle-import:SOT143")
      (libsource (lib "eagle-import") (part "MIC5018"))
    )
    (comp (ref "U$27")
      (value "AP9101C")
      (footprint "eagle-import:SOT25")
      (libsource (lib "eagle-import") (part "AP9101C"))
    )
    (comp (ref "U8")
      (value "MCP73831")
      (footprint "eagle-import:SOT23-5")
      (libsource (lib "eagle-import") (part "MCP73831"))
    )
    (comp (ref "C8")
      (value "10uF")
      (footprint "eagle-import:0603-CAP")
      (libsource (lib "eagle-import") (part "SparkFun-Passives_CAP0603-CAP"))
    )
    (comp (ref "C9")
      (value "1uF")
      (footprint "eagle-import:0603-CAP")
      (libsource (lib "eagle-import") (part "SparkFun-Passives_CAP0603-CAP"))
    )
    (comp (ref "C13")
      (value "330pF")
      (footprint "eagle-import:0603-CAP")
      (libsource (lib "eagle-import") (part "SparkFun-Passives_CAP0603-CAP"))
    )
    (comp (ref "C14")
      (value "0.1uF")
      (footprint "eagle-import:0603-CAP")
      (libsource (lib "eagle-import") (part "SparkFun-Passives_CAP0603-CAP"))
    )
    (comp (ref "C15")
      (value "10uF")
      (footprint "eagle-import:0603-CAP")
      (libsource (lib "eagle-import") (part "SparkFun-Passives_CAP0603-CAP"))
    )
    (comp (ref "C16")
      (value "10uF")
      (footprint "eagle-import:0603-CAP")
      (libsource (lib "eagle-import") (part "SparkFun-Passives_CAP0603-CAP"))
    )
    (comp (ref "C17")
      (value "0.1uF")
      (footprint "eagle-import:0603-CAP")
      (libsource (lib "eagle-import") (part "SparkFun-Passives_CAP0603-CAP"))
    )
    (comp (ref "C18")
      (value "10uF")
      (footprint "eagle-import:0603-CAP")
      (libsource (lib "eagle-import") (part "SparkFun-Passives_CAP0603-CAP"))
    )
    (comp (ref "C19")
      (value "0.1uF")
      (footprint "eagle-import:0603-CAP")
      (libsource (lib "eagle-import") (part "SparkFun-Passives_CAP0603-CAP"))
    )
    (comp (ref "C20")
      (value "10uF")
      (footprint "eagle-import:0603-CAP")
      (libsource (lib "eagle-import") (part "SparkFun-Passives_CAP0603-CAP"))
    )
    (comp (ref "C21")
      (value "10uF")
      (footprint "eagle-import:0603-CAP")
      (libsource (lib "eagle-import") (part "SparkFun-Passives_CAP0603-CAP"))
    )
    (comp (ref "C22")
      (value "1uF")
      (footprint "eagle-import:0603-CAP")
      (libsource (lib "eagle-import") (part "SparkFun-Passives_CAP0603-CAP"))
    )
    (comp (ref "C43")
      (value "47uF")
      (footprint "eagle-import:EIA3216")
      (libsource (lib "eagle-import") (part "CAP_POL1206"))
    )
    (comp (ref "C60")
      (value "10uF")
      (footprint "eagle-import:0603-CAP")
      (libsource (lib "eagle-import") (part "SparkFun-Passives_CAP0603-CAP"))
    )
    (comp (ref "D1")
      (value "DIODE-BAS16J")
      (footprint "eagle-import:SOD-323")
      (libsource (lib "eagle-import") (part "DIODE-BAS16J"))
    )
    (comp (ref "L2")
      (value "10uH")
      (footprint "eagle-import:1210")
      (libsource (lib "eagle-import") (part "INDUCTOR1210"))
    )
    (comp (ref "L3")
      (value "10uH")
      (footprint "eagle-import:1210")
      (libsource (lib "eagle-import") (part "INDUCTOR1210"))
    )
    (comp (ref "L7")
      (value "10uH")
      (footprint "eagle-import:1210")
      (libsource (lib "eagle-import") (part "INDUCTOR1210"))
    )
    (comp (ref "R9")
      (value "RESISTOR1206")
      (footprint "eagle-import:1206")
      (libsource (lib "eagle-import") (part "RESISTOR1206"))
    )
    (comp (ref "R12")
      (value "10k")
      (footprint "eagle-import:0603-RES")
      (libsource (lib "eagle-import") (part "RESISTOR0603-RES"))
    )
    (comp (ref "R18")
      (value "75k")
      (footprint "eagle-import:0603-RES")
      (libsource (lib "eagle-import") (part "RESISTOR0603-RES"))
    )
    (comp (ref "R19")
      (value "13.3K")
      (footprint "eagle-import:0603-RES")
      (libsource (lib "eagle-import") (part "RESISTOR0603-RES"))
    )
    (comp (ref "R26")
      (value "RESISTOR1206")
      (footprint "eagle-import:1206")
      (libsource (lib "eagle-import") (part "RESISTOR1206"))
    )
    (comp (ref "R27")
      (value "RESISTOR1206")
      (footprint "eagle-import:1206")
      (libsource (lib "eagle-import") (part "RESISTOR1206"))
    )
    (comp (ref "R28")
      (value "RESISTOR1206")
      (footprint "eagle-import:1206")
      (libsource (lib "eagle-import") (part "RESISTOR1206"))
    )
    (comp (ref "U$4")
      (value "LM2731")
      (footprint "eagle-import:SOT23-5")
      (libsource (lib "eagle-import") (part "LM2731"))
    )
    (comp (ref "U$6")
      (value "ADP3333")
      (footprint "eagle-import:MSOP-8")
      (libsource (lib "eagle-import") (part "ADP3333"))
    )
    (comp (ref "U$37")
      (value "SHEILD2")
      (footprint "eagle-import:SHIELD_BMI-S-209-C")
      (libsource (lib "eagle-import") (part "SHEILD2"))
    )
    (comp (ref "C32")
      (value "10uF")
      (footprint "eagle-import:0603-CAP")
      (libsource (lib "eagle-import") (part "CAP0603-CAP"))
    )
    (comp (ref "C33")
      (value "0.1uF")
      (footprint "eagle-import:0603-CAP")
      (libsource (lib "eagle-import") (part "SparkFun-Passives_CAP0603-CAP"))
    )
    (comp (ref "C34")
      (value "0.1uF")
      (footprint "eagle-import:0603-CAP")
      (libsource (lib "eagle-import") (part "SparkFun-Passives_CAP0603-CAP"))
    )
    (comp (ref "C35")
      (value "1uF")
      (footprint "eagle-import:0603-CAP")
      (libsource (lib "eagle-import") (part "SparkFun-Passives_CAP0603-CAP"))
    )
    (comp (ref "C46")
      (value "0.1uF")
      (footprint "eagle-import:0603-CAP")
      (libsource (lib "eagle-import") (part "CAP0603-CAP"))
    )
    (comp (ref "C47")
      (value "0.1uF")
      (footprint "eagle-import:0603-CAP")
      (libsource (lib "eagle-import") (part "CAP0603-CAP"))
    )
    (comp (ref "C48")
      (value "0.1uF")
      (footprint "eagle-import:0603-CAP")
      (libsource (lib "eagle-import") (part "CAP0603-CAP"))
    )
    (comp (ref "C49")
      (value "0.1u")
      (footprint "eagle-import:0603-CAP")
      (libsource (lib "eagle-import") (part "CAP0603-CAP"))
    )
    (comp (ref "C50")
      (value "10uF")
      (footprint "eagle-import:0603-CAP")
      (libsource (lib "eagle-import") (part "CAP0603-CAP"))
    )
    (comp (ref "C55")
      (value "0.1uF")
      (footprint "eagle-import:0603-CAP")
      (libsource (lib "eagle-import") (part "CAP0603-CAP"))
    )
    (comp (ref "C59")
      (value "10uF")
      (footprint "eagle-import:0603-CAP")
      (libsource (lib "eagle-import") (part "CAP0603-CAP"))
    )
    (comp (ref "C61")
      (value "1uF")
      (footprint "eagle-import:0603-CAP")
      (libsource (lib "eagle-import") (part "SparkFun-Passives_CAP0603-CAP"))
    )
    (comp (ref "C62")
      (value "1uF")
      (footprint "eagle-import:0603-CAP")
      (libsource (lib "eagle-import") (part "SparkFun-Passives_CAP0603-CAP"))
    )
    (comp (ref "C63")
      (value "1uF")
      (footprint "eagle-import:0603-CAP")
      (libsource (lib "eagle-import") (part "SparkFun-Passives_CAP0603-CAP"))
    )
    (comp (ref "C64")
      (value "1uF")
      (footprint "eagle-import:0603-CAP")
      (libsource (lib "eagle-import") (part "SparkFun-Passives_CAP0603-CAP"))
    )
    (comp (ref "C65")
      (value "1uF")
      (footprint "eagle-import:0603-CAP")
      (libsource (lib "eagle-import") (part "SparkFun-Passives_CAP0603-CAP"))
    )
    (comp (ref "C66")
      (value "1uF")
      (footprint "eagle-import:0603-CAP")
      (libsource (lib "eagle-import") (part "SparkFun-Passives_CAP0603-CAP"))
    )
    (comp (ref "C67")
      (value "10uF")
      (footprint "eagle-import:0603-CAP")
      (libsource (lib "eagle-import") (part "CAP0603-CAP"))
    )
    (comp (ref "C70")
      (value "1uF")
      (footprint "eagle-import:0603-CAP")
      (libsource (lib "eagle-import") (part "SparkFun-Passives_CAP0603-CAP"))
    )
    (comp (ref "C71")
      (value "1uF")
      (footprint "eagle-import:0603-CAP")
      (libsource (lib "eagle-import") (part "SparkFun-Passives_CAP0603-CAP"))
    )
    (comp (ref "C72")
      (value "1uF")
      (footprint "eagle-import:0603-CAP")
      (libsource (lib "eagle-import") (part "SparkFun-Passives_CAP0603-CAP"))
    )
    (comp (ref "R46")
      (value "510")
      (footprint "eagle-import:0603-RES")
      (libsource (lib "eagle-import") (part "RESISTOR0603-RES"))
    )
    (comp (ref "R47")
      (value "510")
      (footprint "eagle-import:0603-RES")
      (libsource (lib "eagle-import") (part "RESISTOR0603-RES"))
    )
    (comp (ref "R48")
      (value "510")
      (footprint "eagle-import:0603-RES")
      (libsource (lib "eagle-import") (part "RESISTOR0603-RES"))
    )
    (comp (ref "R49")
      (value "510")
      (footprint "eagle-import:0603-RES")
      (libsource (lib "eagle-import") (part "RESISTOR0603-RES"))
    )
    (comp (ref "R50")
      (value "510")
      (footprint "eagle-import:0603-RES")
      (libsource (lib "eagle-import") (part "RESISTOR0603-RES"))
    )
    (comp (ref "R51")
      (value "510")
      (footprint "eagle-import:0603-RES")
      (libsource (lib "eagle-import") (part "RESISTOR0603-RES"))
    )
    (comp (ref "R52")
      (value "47")
      (footprint "eagle-import:0603-RES")
      (libsource (lib "eagle-import") (part "RESISTOR0603-RES"))
    )
    (comp (ref "R56")
      (value "47")
      (footprint "eagle-import:0603-RES")
      (libsource (lib "eagle-import") (part "RESISTOR0603-RES"))
    )
    (comp (ref "R57")
      (value "220")
      (footprint "eagle-import:0603-RES")
      (libsource (lib "eagle-import") (part "RESISTOR0603-RES"))
    )
    (comp (ref "R58")
      (value "10k")
      (footprint "eagle-import:0603-RES")
      (libsource (lib "eagle-import") (part "RESISTOR0603-RES"))
    )
    (comp (ref "R63")
      (value "47")
      (footprint "eagle-import:0603-RES")
      (libsource (lib "eagle-import") (part "RESISTOR0603-RES"))
    )
    (comp (ref "R64")
      (value "47")
      (footprint "eagle-import:0603-RES")
      (libsource (lib "eagle-import") (part "RESISTOR0603-RES"))
    )
    (comp (ref "R66")
      (value "47")
      (footprint "eagle-import:0603-RES")
      (libsource (lib "eagle-import") (part "RESISTOR0603-RES"))
    )
    (comp (ref "R67")
      (value "47")
      (footprint "eagle-import:0603-RES")
      (libsource (lib "eagle-import") (part "RESISTOR0603-RES"))
    )
    (comp (ref "R82")
      (value "47")
      (footprint "eagle-import:0603-RES")
      (libsource (lib "eagle-import") (part "RESISTOR0603-RES"))
    )
    (comp (ref "SJ1")
      (value "JUMPER-PAD-2-NC_BY_TRACE")
      (footprint "eagle-import:PAD-JUMPER-2-NC_BY_TRACE_YES_SILK")
      (libsource (lib "eagle-import") (part "JUMPER-PAD-2-NC_BY_TRACE"))
    )
    (comp (ref "U$7")
      (value "ADS1248")
      (footprint "eagle-import:TSSOP28")
      (libsource (lib "eagle-import") (part "ADS1248"))
    )
    (comp (ref "U$11")
      (value "HMC1002")
      (footprint "eagle-import:SOIC20R")
      (libsource (lib "eagle-import") (part "HMC1002"))
    )
    (comp (ref "U$12")
      (value "HMC1001")
      (footprint "eagle-import:HMC1001")
      (libsource (lib "eagle-import") (part "HMC1001"))
    )
    (comp (ref "U$17")
      (value "IRF7509")
      (footprint "eagle-import:MICRO8")
      (libsource (lib "eagle-import") (part "IRF7509"))
    )
    (comp (ref "U$22")
      (value "ADR441")
      (footprint "eagle-import:SOIC8")
      (libsource (lib "eagle-import") (part "ADR441"))
    )
  )
  (nets
    (net (code "8") (name "(WR)PG0") (class "Default")
      (node (ref "U1") (pin "51") (pinfunction "(WR)PG0_51") (pintype "bidirectional"))
    )
    (net (code "14") (name "3.3V") (class "Default")
      (node (ref "JP13") (pin "1") (pinfunction "1_1") (pintype "passive"))
      (node (ref "JP13") (pin "2") (pinfunction "2_2") (pintype "passive"))
      (node (ref "Q3") (pin "1") (pinfunction "G_1") (pintype "passive"))
      (node (ref "R11") (pin "2") (pinfunction "2_2") (pintype "passive"))
      (node (ref "R13") (pin "2") (pinfunction "2_2") (pintype "passive"))
      (node (ref "R16") (pin "2") (pinfunction "2_2") (pintype "passive"))
      (node (ref "R23") (pin "2") (pinfunction "2_2") (pintype "passive"))
      (node (ref "R3") (pin "1") (pinfunction "1_1") (pintype "passive"))
      (node (ref "R32") (pin "2") (pinfunction "2_2") (pintype "passive"))
      (node (ref "R34") (pin "2") (pinfunction "2_2") (pintype "passive"))
      (node (ref "R4") (pin "2") (pinfunction "2_2") (pintype "passive"))
      (node (ref "R44") (pin "1") (pinfunction "1_1") (pintype "passive"))
      (node (ref "R5") (pin "2") (pinfunction "2_2") (pintype "passive"))
      (node (ref "T1") (pin "4") (pinfunction "S_4") (pintype "passive"))
      (node (ref "U$1") (pin "1") (pinfunction "VCC_1") (pintype "bidirectional"))
      (node (ref "U$3") (pin "5") (pinfunction "VCC_5") (pintype "bidirectional"))
      (node (ref "U1") (pin "84") (pinfunction "PK5(ADC13/PCINT21)_84") (pintype "bidirectional"))
      (node (ref "U2") (pin "VCC") (pinfunction "VCC_VCC") (pintype "bidirectional"))
      (node (ref "U3") (pin "18") (pinfunction "VBAT_18") (pintype "bidirectional"))
      (node (ref "U4") (pin "1") (pinfunction "VREF1_1") (pintype "bidirectional"))
      (node (ref "U6") (pin "15") (pinfunction "VDD_15") (pintype "bidirectional"))
      (node (ref "U6") (pin "16") (pinfunction "VDD_16") (pintype "bidirectional"))
      (node (ref "U6") (pin "17") (pinfunction "VDD_17") (pintype "bidirectional"))
      (node (ref "U6") (pin "18") (pinfunction "VDD_IO_18") (pintype "bidirectional"))
      (node (ref "U7") (pin "1") (pinfunction "VDD_1") (pintype "power_in"))
      (node (ref "U9") (pin "1") (pinfunction "VDD_1") (pintype "power_in"))
      (node (ref "U9") (pin "2") (pinfunction "ADDR_2") (pintype "input"))
    )
    (net (code "15") (name "3.3_VOUT") (class "Default")
      (node (ref "C24") (pin "1") (pinfunction "1_1") (pintype "passive"))
      (node (ref "C25") (pin "1") (pinfunction "1_1") (pintype "passive"))
      (node (ref "C31") (pin "A") (pinfunction "+_A") (pintype "passive"))
      (node (ref "R3") (pin "2") (pinfunction "2_2") (pintype "passive"))
      (node (ref "U5") (pin "10") (pinfunction "FB_10") (pintype "passive"))
      (node (ref "U5") (pin "2") (pinfunction "VOUT_2") (pintype "passive"))
    )
    (net (code "16") (name "5V") (class "Default")
      (node (ref "C1") (pin "1") (pinfunction "1_1") (pintype "passive"))
      (node (ref "C2") (pin "1") (pinfunction "1_1") (pintype "passive"))
      (node (ref "C3") (pin "1") (pinfunction "1_1") (pintype "passive"))
      (node (ref "JP12") (pin "1") (pinfunction "1_1") (pintype "passive"))
      (node (ref "JP12") (pin "2") (pinfunction "2_2") (pintype "passive"))
      (node (ref "R17") (pin "1") (pinfunction "1_1") (pintype "passive"))
      (node (ref "R22") (pin "2") (pinfunction "2_2") (pintype "passive"))
      (node (ref "R45") (pin "1") (pinfunction "1_1") (pintype "passive"))
      (node (ref "R6") (pin "2") (pinfunction "2_2") (pintype "passive"))
      (node (ref "R7") (pin "2") (pinfunction "2_2") (pintype "passive"))
      (node (ref "R8") (pin "2") (pinfunction "2_2") (pintype "passive"))
      (node (ref "U$24") (pin "3") (pinfunction "VDD_3") (pintype "bidirectional"))
      (node (ref "U$25") (pin "3") (pinfunction "VDD_3") (pintype "bidirectional"))
      (node (ref "U$47") (pin "3") (pinfunction "VDD_3") (pintype "bidirectional"))
      (node (ref "U$48") (pin "3") (pinfunction "VDD_3") (pintype "bidirectional"))
      (node (ref "U1") (pin "10") (pinfunction "VCC_10") (pintype "power_in"))
      (node (ref "U1") (pin "100") (pinfunction "AVCC_100") (pintype "power_in"))
      (node (ref "U1") (pin "31") (pinfunction "VCC1_31") (pintype "power_in"))
      (node (ref "U1") (pin "61") (pinfunction "VCC2_61") (pintype "power_in"))
      (node (ref "U1") (pin "80") (pinfunction "VCC3_80") (pintype "power_in"))
      (node (ref "U1") (pin "86") (pinfunction "PK3(ADC11/PCINT19)_86") (pintype "bidirectional"))
    )
    (net (code "17") (name "5V_OUT") (class "Default")
      (node (ref "C30") (pin "A") (pinfunction "+_A") (pintype "passive"))
      (node (ref "C44") (pin "1") (pinfunction "1_1") (pintype "passive"))
      (node (ref "C56") (pin "1") (pinfunction "1_1") (pintype "passive"))
      (node (ref "R17") (pin "2") (pinfunction "2_2") (pintype "passive"))
      (node (ref "U11") (pin "10") (pinfunction "FB_10") (pintype "passive"))
      (node (ref "U11") (pin "2") (pinfunction "VOUT_2") (pintype "passive"))
    )
    (net (code "18") (name "8.5V_OUT") (class "Default")
      (node (ref "L2") (pin "1") (pinfunction "1_1") (pintype "passive"))
      (node (ref "R26") (pin "2") (pinfunction "2_2") (pintype "passive"))
    )
    (net (code "19") (name "ADP_IN") (class "Default")
      (node (ref "C22") (pin "1") (pinfunction "1_1") (pintype "passive"))
      (node (ref "R28") (pin "2") (pinfunction "2_2") (pintype "passive"))
      (node (ref "U$6") (pin "2") (pinfunction "VIN_2") (pintype "bidirectional"))
      (node (ref "U$6") (pin "7") (pinfunction "SD_7") (pintype "bidirectional"))
    )
    (net (code "20") (name "AREF") (class "Default")
      (node (ref "C6") (pin "1") (pinfunction "1_1") (pintype "passive"))
      (node (ref "U1") (pin "98") (pinfunction "AREF_98") (pintype "bidirectional"))
    )
    (net (code "21") (name "ATMEGA2560") (class "Default")
      (node (ref "Q3") (pin "2") (pinfunction "S_2") (pintype "passive"))
      (node (ref "R23") (pin "1") (pinfunction "1_1") (pintype "passive"))
      (node (ref "U3") (pin "42") (pinfunction "RXD0_42") (pintype "bidirectional"))
    )
    (net (code "22") (name "BATTERY_CHARGE_IN") (class "Default")
      (node (ref "C53") (pin "1") (pinfunction "1_1") (pintype "passive"))
      (node (ref "D2") (pin "A") (pinfunction "A_A") (pintype "passive"))
      (node (ref "D3") (pin "A") (pinfunction "A_A") (pintype "passive"))
      (node (ref "D6") (pin "A") (pinfunction "A_A") (pintype "passive"))
      (node (ref "JP5") (pin "VBUS") (pinfunction "VBUS_VBUS") (pintype "bidirectional"))
      (node (ref "Q10") (pin "1") (pinfunction "G_1") (pintype "bidirectional"))
      (node (ref "Q4") (pin "S1") (pinfunction "S_S1") (pintype "passive"))
      (node (ref "Q4") (pin "S2") (pinfunction "S_S2") (pintype "passive"))
      (node (ref "Q4") (pin "S3") (pinfunction "S_S3") (pintype "passive"))
      (node (ref "R53") (pin "2") (pinfunction "2_2") (pintype "passive"))
      (node (ref "R73") (pin "2") (pinfunction "2_2") (pintype "passive"))
      (node (ref "U8") (pin "4") (pinfunction "VIN_4") (pintype "power_in"))
    )
    (net (code "23") (name "BATTERY_POS") (class "Default")
      (node (ref "C45") (pin "A") (pinfunction "+_A") (pintype "passive"))
      (node (ref "C52") (pin "1") (pinfunction "1_1") (pintype "passive"))
      (node (ref "C68") (pin "A") (pinfunction "+_A") (pintype "passive"))
      (node (ref "C69") (pin "A") (pinfunction "+_A") (pintype "passive"))
      (node (ref "Q10") (pin "3") (pinfunction "D_3") (pintype "bidirectional"))
      (node (ref "R54") (pin "1") (pinfunction "1_1") (pintype "passive"))
      (node (ref "R59") (pin "1") (pinfunction "1_1") (pintype "passive"))
      (node (ref "R73") (pin "1") (pinfunction "1_1") (pintype "passive"))
      (node (ref "U$18") (pin "+") (pinfunction "+_+") (pintype "bidirectional"))
      (node (ref "U8") (pin "3") (pinfunction "VBAT_3") (pintype "power_in"))
    )
    (net (code "24") (name "BATT_OUT") (class "Default")
      (node (ref "Q7") (pin "S1") (pinfunction "S_S1") (pintype "passive"))
      (node (ref "Q7") (pin "S2") (pinfunction "S_S2") (pintype "passive"))
      (node (ref "Q7") (pin "S3") (pinfunction "S_S3") (pintype "passive"))
      (node (ref "R25") (pin "2") (pinfunction "2_2") (pintype "passive"))
      (node (ref "R36") (pin "2") (pinfunction "2_2") (pintype "passive"))
      (node (ref "R9") (pin "1") (pinfunction "1_1") (pintype "passive"))
      (node (ref "U$50") (pin "3") (pinfunction "3_3") (pintype "bidirectional"))
      (node (ref "U1") (pin "77") (pinfunction "(AD1)PA1_77") (pintype "bidirectional"))
      (node (ref "U1") (pin "87") (pinfunction "PK2(ADC10/PCINT18)_87") (pintype "bidirectional"))
    )
    (net (code "25") (name "BAT_INPUT") (class "Default")
      (node (ref "D6") (pin "C") (pinfunction "C_C") (pintype "passive"))
      (node (ref "Q10") (pin "2") (pinfunction "S_2") (pintype "bidirectional"))
      (node (ref "Q5") (pin "D1") (pinfunction "D_D1") (pintype "passive"))
      (node (ref "Q5") (pin "D2") (pinfunction "D_D2") (pintype "passive"))
      (node (ref "Q5") (pin "D3") (pinfunction "D_D3") (pintype "passive"))
      (node (ref "Q5") (pin "D4") (pinfunction "D_D4") (pintype "passive"))
      (node (ref "Q5") (pin "DPAD") (pinfunction "D_DPAD") (pintype "passive"))
      (node (ref "R59") (pin "2") (pinfunction "2_2") (pintype "passive"))
      (node (ref "S1") (pin "COM") (pinfunction "COM_COM") (pintype "passive"))
    )
    (net (code "26") (name "BAT_NEG") (class "Default")
      (node (ref "C45") (pin "C") (pinfunction "-_C") (pintype "passive"))
      (node (ref "C52") (pin "2") (pinfunction "2_2") (pintype "passive"))
      (node (ref "C53") (pin "2") (pinfunction "2_2") (pintype "passive"))
      (node (ref "C68") (pin "C") (pinfunction "-_C") (pintype "passive"))
      (node (ref "C69") (pin "C") (pinfunction "-_C") (pintype "passive"))
      (node (ref "JP5") (pin "GND") (pinfunction "GND_GND") (pintype "bidirectional"))
      (node (ref "JP5") (pin "MT1") (pinfunction "GND_MT1") (pintype "bidirectional"))
      (node (ref "JP5") (pin "MT2") (pinfunction "GND_MT2") (pintype "bidirectional"))
      (node (ref "Q8") (pin "S1") (pinfunction "S_S1") (pintype "passive"))
      (node (ref "Q8") (pin "S2") (pinfunction "S_S2") (pintype "passive"))
      (node (ref "Q8") (pin "S3") (pinfunction "S_S3") (pintype "passive"))
      (node (ref "Q9") (pin "2") (pinfunction "S_2") (pintype "passive"))
      (node (ref "R53") (pin "1") (pinfunction "1_1") (pintype "passive"))
      (node (ref "R55") (pin "1") (pinfunction "1_1") (pintype "passive"))
      (node (ref "R62") (pin "1") (pinfunction "1_1") (pintype "passive"))
      (node (ref "R83") (pin "1") (pinfunction "1_1") (pintype "passive"))
      (node (ref "S4") (pin "COM") (pinfunction "COM_COM") (pintype "passive"))
      (node (ref "U8") (pin "2") (pinfunction "VSS_2") (pintype "power_in"))
    )
    (net (code "27") (name "BAT_NEG_PROT") (class "Default")
      (node (ref "C51") (pin "2") (pinfunction "2_2") (pintype "passive"))
      (node (ref "Q11") (pin "2") (pinfunction "S_2") (pintype "passive"))
      (node (ref "U$18") (pin "-") (pinfunction "-_-") (pintype "bidirectional"))
      (node (ref "U$27") (pin "3") (pinfunction "VSS_3") (pintype "bidirectional"))
    )
    (net (code "28") (name "CS_ADS") (class "Default")
      (node (ref "R67") (pin "2") (pinfunction "2_2") (pintype "passive"))
      (node (ref "U1") (pin "15") (pinfunction "PH3(OC4A)_15") (pintype "bidirectional"))
    )
    (net (code "29") (name "CS_ISL_MAG") (class "Default")
      (node (ref "U1") (pin "7") (pinfunction "(OC3C/INT5)PE5_7") (pintype "bidirectional"))
    )
    (net (code "30") (name "DRDY_ADS") (class "Default")
      (node (ref "R66") (pin "2") (pinfunction "2_2") (pintype "passive"))
      (node (ref "U1") (pin "16") (pinfunction "PH4(OC4B)_16") (pintype "bidirectional"))
    )
    (net (code "31") (name "ENABLE") (class "Default")
      (node (ref "R12") (pin "2") (pinfunction "2_2") (pintype "passive"))
      (node (ref "R21") (pin "2") (pinfunction "2_2") (pintype "passive"))
      (node (ref "R32") (pin "1") (pinfunction "1_1") (pintype "passive"))
      (node (ref "U$4") (pin "4") (pinfunction "SD_4") (pintype "bidirectional"))
      (node (ref "U11") (pin "6") (pinfunction "EN_6") (pintype "input"))
    )
    (net (code "32") (name "FB_LM2731") (class "Default")
      (node (ref "C13") (pin "2") (pinfunction "2_2") (pintype "passive"))
      (node (ref "R18") (pin "1") (pinfunction "1_1") (pintype "passive"))
      (node (ref "R19") (pin "2") (pinfunction "2_2") (pintype "passive"))
      (node (ref "U$4") (pin "3") (pinfunction "FB_3") (pintype "bidirectional"))
    )
    (net (code "33") (name "GND") (class "Default")
      (node (ref "C1") (pin "2") (pinfunction "2_2") (pintype "passive"))
      (node (ref "C10") (pin "1") (pinfunction "1_1") (pintype "passive"))
      (node (ref "C12") (pin "1") (pinfunction "1_1") (pintype "passive"))
      (node (ref "C14") (pin "2") (pinfunction "2_2") (pintype "passive"))
      (node (ref "C15") (pin "2") (pinfunction "2_2") (pintype "passive"))
      (node (ref "C16") (pin "2") (pinfunction "2_2") (pintype "passive"))
      (node (ref "C17") (pin "2") (pinfunction "2_2") (pintype "passive"))
      (node (ref "C18") (pin "2") (pinfunction "2_2") (pintype "passive"))
      (node (ref "C19") (pin "2") (pinfunction "2_2") (pintype "passive"))
      (node (ref "C2") (pin "2") (pinfunction "2_2") (pintype "passive"))
      (node (ref "C20") (pin "2") (pinfunction "2_2") (pintype "passive"))
      (node (ref "C21") (pin "2") (pinfunction "2_2") (pintype "passive"))
      (node (ref "C22") (pin "2") (pinfunction "2_2") (pintype "passive"))
      (node (ref "C23") (pin "2") (pinfunction "2_2") (pintype "passive"))
      (node (ref "C24") (pin "2") (pinfunction "2_2") (pintype "passive"))
      (node (ref "C25") (pin "2") (pinfunction "2_2") (pintype "passive"))
      (node (ref "C26") (pin "2") (pinfunction "2_2") (pintype "passive"))
      (node (ref "C27") (pin "2") (pinfunction "2_2") (pintype "passive"))
      (node (ref "C28") (pin "C") (pinfunction "-_C") (pintype "passive"))
      (node (ref "C29") (pin "C") (pinfunction "-_C") (pintype "passive"))
      (node (ref "C3") (pin "2") (pinfunction "2_2") (pintype "passive"))
      (node (ref "C30") (pin "C") (pinfunction "-_C") (pintype "passive"))
      (node (ref "C31") (pin "C") (pinfunction "-_C") (pintype "passive"))
      (node (ref "C32") (pin "2") (pinfunction "2_2") (pintype "passive"))
      (node (ref "C36") (pin "2") (pinfunction "2_2") (pintype "passive"))
      (node (ref "C37") (pin "2") (pinfunction "2_2") (pintype "passive"))
      (node (ref "C38") (pin "2") (pinfunction "2_2") (pintype "passive"))
      (node (ref "C39") (pin "2") (pinfunction "2_2") (pintype "passive"))
      (node (ref "C40") (pin "2") (pinfunction "2_2") (pintype "passive"))
      (node (ref "C41") (pin "2") (pinfunction "2_2") (pintype "passive"))
      (node (ref "C42") (pin "2") (pinfunction "2_2") (pintype "passive"))
      (node (ref "C43") (pin "C") (pinfunction "-_C") (pintype "passive"))
      (node (ref "C44") (pin "2") (pinfunction "2_2") (pintype "passive"))
      (node (ref "C46") (pin "2") (pinfunction "2_2") (pintype "passive"))
      (node (ref "C47") (pin "2") (pinfunction "2_2") (pintype "passive"))
      (node (ref "C5") (pin "1") (pinfunction "1_1") (pintype "passive"))
      (node (ref "C54") (pin "2") (pinfunction "2_2") (pintype "passive"))
      (node (ref "C56") (pin "2") (pinfunction "2_2") (pintype "passive"))
      (node (ref "C57") (pin "2") (pinfunction "2_2") (pintype "passive"))
      (node (ref "C58") (pin "2") (pinfunction "2_2") (pintype "passive"))
      (node (ref "C6") (pin "2") (pinfunction "2_2") (pintype "passive"))
      (node (ref "C60") (pin "2") (pinfunction "2_2") (pintype "passive"))
      (node (ref "C67") (pin "2") (pinfunction "2_2") (pintype "passive"))
      (node (ref "C7") (pin "2") (pinfunction "2_2") (pintype "passive"))
      (node (ref "C73") (pin "2") (pinfunction "2_2") (pintype "passive"))
      (node (ref "C74") (pin "2") (pinfunction "2_2") (pintype "passive"))
      (node (ref "C75") (pin "2") (pinfunction "2_2") (pintype "passive"))
      (node (ref "C8") (pin "2") (pinfunction "2_2") (pintype "passive"))
      (node (ref "C9") (pin "2") (pinfunction "2_2") (pintype "passive"))
      (node (ref "D4") (pin "C") (pinfunction "C_C") (pintype "passive"))
      (node (ref "D5") (pin "C") (pinfunction "C_C") (pintype "passive"))
      (node (ref "J1") (pin "P$2") (pinfunction "2_P$2") (pintype "passive"))
      (node (ref "J3") (pin "P$2") (pinfunction "2_P$2") (pintype "passive"))
      (node (ref "JP14") (pin "1") (pinfunction "1_1") (pintype "passive"))
      (node (ref "JP14") (pin "2") (pinfunction "2_2") (pintype "passive"))
      (node (ref "PT1") (pin "P$1") (pinfunction "P$1_P$1") (pintype "bidirectional"))
      (node (ref "Q8") (pin "D1") (pinfunction "D_D1") (pintype "passive"))
      (node (ref "Q8") (pin "D2") (pinfunction "D_D2") (pintype "passive"))
      (node (ref "Q8") (pin "D3") (pinfunction "D_D3") (pintype "passive"))
      (node (ref "Q8") (pin "D4") (pinfunction "D_D4") (pintype "passive"))
      (node (ref "Q8") (pin "DPAD") (pinfunction "D_DPAD") (pintype "passive"))
      (node (ref "R12") (pin "1") (pinfunction "1_1") (pintype "passive"))
      (node (ref "R15") (pin "1") (pinfunction "1_1") (pintype "passive"))
      (node (ref "R19") (pin "1") (pinfunction "1_1") (pintype "passive"))
      (node (ref "R2") (pin "1") (pinfunction "1_1") (pintype "passive"))
      (node (ref "R20") (pin "1") (pinfunction "1_1") (pintype "passive"))
      (node (ref "R21") (pin "1") (pinfunction "1_1") (pintype "passive"))
      (node (ref "R24") (pin "1") (pinfunction "1_1") (pintype "passive"))
      (node (ref "R29") (pin "1") (pinfunction "1_1") (pintype "passive"))
      (node (ref "R31") (pin "1") (pinfunction "1_1") (pintype "passive"))
      (node (ref "R33") (pin "1") (pinfunction "1_1") (pintype "passive"))
      (node (ref "R35") (pin "1") (pinfunction "1_1") (pintype "passive"))
      (node (ref "R37") (pin "1") (pinfunction "1_1") (pintype "passive"))
      (node (ref "R38") (pin "1") (pinfunction "1_1") (pintype "passive"))
      (node (ref "R39") (pin "1") (pinfunction "1_1") (pintype "passive"))
      (node (ref "R40") (pin "1") (pinfunction "1_1") (pintype "passive"))
      (node (ref "R41") (pin "2") (pinfunction "2_2") (pintype "passive"))
      (node (ref "R42") (pin "1") (pinfunction "1_1") (pintype "passive"))
      (node (ref "R43") (pin "1") (pinfunction "1_1") (pintype "passive"))
      (node (ref "S4") (pin "NC") (pinfunction "NC_NC") (pintype "passive"))
      (node (ref "SJ1") (pin "2") (pinfunction "2_2") (pintype "passive"))
      (node (ref "U$1") (pin "8") (pinfunction "GND_8") (pintype "bidirectional"))
      (node (ref "U$13") (pin "1") (pinfunction "GND_1") (pintype "bidirectional"))
      (node (ref "U$14") (pin "1") (pinfunction "GND_1") (pintype "bidirectional"))
      (node (ref "U$15") (pin "1") (pinfunction "GND_1") (pintype "bidirectional"))
      (node (ref "U$16") (pin "1") (pinfunction "GND_1") (pintype "bidirectional"))
      (node (ref "U$19") (pin "1") (pinfunction "GND_1") (pintype "bidirectional"))
      (node (ref "U$20") (pin "1") (pinfunction "GND_1") (pintype "bidirectional"))
      (node (ref "U$24") (pin "5") (pinfunction "GND_5") (pintype "bidirectional"))
      (node (ref "U$25") (pin "5") (pinfunction "GND_5") (pintype "bidirectional"))
      (node (ref "U$3") (pin "16") (pinfunction "GND_16") (pintype "power_in"))
      (node (ref "U$3") (pin "2") (pinfunction "GND_2") (pintype "power_in"))
      (node (ref "U$3") (pin "9") (pinfunction "GND_9") (pintype "power_in"))
      (node (ref "U$37") (pin "P$1") (pinfunction "P$1_P$1") (pintype "bidirectional"))
      (node (ref "U$37") (pin "P$10") (pinfunction "P$1_P$10") (pintype "bidirectional"))
      (node (ref "U$37") (pin "P$11") (pinfunction "P$1_P$11") (pintype "bidirectional"))
      (node (ref "U$37") (pin "P$12") (pinfunction "P$1_P$12") (pintype "bidirectional"))
      (node (ref "U$37") (pin "P$13") (pinfunction "P$1_P$13") (pintype "bidirectional"))
      (node (ref "U$37") (pin "P$14") (pinfunction "P$1_P$14") (pintype "bidirectional"))
      (node (ref "U$37") (pin "P$15") (pinfunction "P$1_P$15") (pintype "bidirectional"))
      (node (ref "U$37") (pin "P$16") (pinfunction "P$1_P$16") (pintype "bidirectional"))
      (node (ref "U$37") (pin "P$2") (pinfunction "P$1_P$2") (pintype "bidirectional"))
      (node (ref "U$37") (pin "P$3") (pinfunction "P$1_P$3") (pintype "bidirectional"))
      (node (ref "U$37") (pin "P$4") (pinfunction "P$1_P$4") (pintype "bidirectional"))
      (node (ref "U$37") (pin "P$5") (pinfunction "P$1_P$5") (pintype "bidirectional"))
      (node (ref "U$37") (pin "P$6") (pinfunction "P$1_P$6") (pintype "bidirectional"))
      (node (ref "U$37") (pin "P$7") (pinfunction "P$1_P$7") (pintype "bidirectional"))
      (node (ref "U$37") (pin "P$8") (pinfunction "P$1_P$8") (pintype "bidirectional"))
      (node (ref "U$37") (pin "P$9") (pinfunction "P$1_P$9") (pintype "bidirectional"))
      (node (ref "U$39") (pin "P$1") (pinfunction "P$1_P$1") (pintype "bidirectional"))
      (node (ref "U$39") (pin "P$10") (pinfunction "P$1_P$10") (pintype "bidirectional"))
      (node (ref "U$39") (pin "P$11") (pinfunction "P$1_P$11") (pintype "bidirectional"))
      (node (ref "U$39") (pin "P$12") (pinfunction "P$1_P$12") (pintype "bidirectional"))
      (node (ref "U$39") (pin "P$2") (pinfunction "P$1_P$2") (pintype "bidirectional"))
      (node (ref "U$39") (pin "P$3") (pinfunction "P$1_P$3") (pintype "bidirectional"))
      (node (ref "U$39") (pin "P$4") (pinfunction "P$1_P$4") (pintype "bidirectional"))
      (node (ref "U$39") (pin "P$5") (pinfunction "P$1_P$5") (pintype "bidirectional"))
      (node (ref "U$39") (pin "P$6") (pinfunction "P$1_P$6") (pintype "bidirectional"))
      (node (ref "U$39") (pin "P$7") (pinfunction "P$1_P$7") (pintype "bidirectional"))
      (node (ref "U$39") (pin "P$8") (pinfunction "P$1_P$8") (pintype "bidirectional"))
      (node (ref "U$39") (pin "P$9") (pinfunction "P$1_P$9") (pintype "bidirectional"))
      (node (ref "U$4") (pin "2") (pinfunction "GND_2") (pintype "bidirectional"))
      (node (ref "U$41") (pin "P$1") (pinfunction "P$1_P$1") (pintype "bidirectional"))
      (node (ref "U$41") (pin "P$10") (pinfunction "P$1_P$10") (pintype "bidirectional"))
      (node (ref "U$41") (pin "P$11") (pinfunction "P$1_P$11") (pintype "bidirectional"))
      (node (ref "U$41") (pin "P$12") (pinfunction "P$1_P$12") (pintype "bidirectional"))
      (node (ref "U$41") (pin "P$2") (pinfunction "P$1_P$2") (pintype "bidirectional"))
      (node (ref "U$41") (pin "P$3") (pinfunction "P$1_P$3") (pintype "bidirectional"))
      (node (ref "U$41") (pin "P$4") (pinfunction "P$1_P$4") (pintype "bidirectional"))
      (node (ref "U$41") (pin "P$5") (pinfunction "P$1_P$5") (pintype "bidirectional"))
      (node (ref "U$41") (pin "P$6") (pinfunction "P$1_P$6") (pintype "bidirectional"))
      (node (ref "U$41") (pin "P$7") (pinfunction "P$1_P$7") (pintype "bidirectional"))
      (node (ref "U$41") (pin "P$8") (pinfunction "P$1_P$8") (pintype "bidirectional"))
      (node (ref "U$41") (pin "P$9") (pinfunction "P$1_P$9") (pintype "bidirectional"))
      (node (ref "U$47") (pin "5") (pinfunction "GND_5") (pintype "bidirectional"))
      (node (ref "U$48") (pin "5") (pinfunction "GND_5") (pintype "bidirectional"))
      (node (ref "U$50") (pin "1") (pinfunction "1_1") (pintype "bidirectional"))
      (node (ref "U$6") (pin "3") (pinfunction "GND_3") (pintype "bidirectional"))
      (node (ref "U$6") (pin "4") (pinfunction "GND_4") (pintype "bidirectional"))
      (node (ref "U$6") (pin "5") (pinfunction "GND_5") (pintype "bidirectional"))
      (node (ref "U$6") (pin "6") (pinfunction "GND_6") (pintype "bidirectional"))
      (node (ref "U$6") (pin "8") (pinfunction "GND_8") (pintype "bidirectional"))
      (node (ref "U$7") (pin "2") (pinfunction "DGND_2") (pintype "bidirectional"))
      (node (ref "U$7") (pin "3") (pinfunction "CLK_3") (pintype "bidirectional"))
      (node (ref "U$8") (pin "1") (pinfunction "GND_1") (pintype "bidirectional"))
      (node (ref "U1") (pin "11") (pinfunction "GND_11") (pintype "power_in"))
      (node (ref "U1") (pin "32") (pinfunction "GND1_32") (pintype "power_in"))
      (node (ref "U1") (pin "62") (pinfunction "GND2_62") (pintype "power_in"))
      (node (ref "U1") (pin "81") (pinfunction "GND3_81") (pintype "power_in"))
      (node (ref "U1") (pin "99") (pinfunction "AGND_99") (pintype "power_in"))
      (node (ref "U11") (pin "11") (pinfunction "PAD_11") (pintype "power_in"))
      (node (ref "U11") (pin "12") (pinfunction "PAD_12") (pintype "power_in"))
      (node (ref "U11") (pin "13") (pinfunction "PAD_13") (pintype "power_in"))
      (node (ref "U11") (pin "14") (pinfunction "PAD_14") (pintype "power_in"))
      (node (ref "U11") (pin "15") (pinfunction "PAD_15") (pintype "power_in"))
      (node (ref "U11") (pin "4") (pinfunction "PGND_4") (pintype "power_in"))
      (node (ref "U11") (pin "9") (pinfunction "GND_9") (pintype "power_in"))
      (node (ref "U2") (pin "CD1") (pinfunction "CD1_CD1") (pintype "bidirectional"))
      (node (ref "U2") (pin "CD2") (pinfunction "CD2_CD2") (pintype "bidirectional"))
      (node (ref "U2") (pin "GND") (pinfunction "GND_GND") (pintype "bidirectional"))
      (node (ref "U2") (pin "GND1") (pinfunction "SHIELD_GND1") (pintype "bidirectional"))
      (node (ref "U2") (pin "GND3") (pinfunction "SHIELD_GND3") (pintype "bidirectional"))
      (node (ref "U3") (pin "10") (pinfunction "GND_10") (pintype "bidirectional"))
      (node (ref "U3") (pin "11") (pinfunction "GND_11") (pintype "bidirectional"))
      (node (ref "U3") (pin "15") (pinfunction "GND_15") (pintype "bidirectional"))
      (node (ref "U3") (pin "19") (pinfunction "GND_19") (pintype "bidirectional"))
      (node (ref "U3") (pin "49") (pinfunction "GND_49") (pintype "bidirectional"))
      (node (ref "U3") (pin "60") (pinfunction "GND_60") (pintype "bidirectional"))
      (node (ref "U3") (pin "64") (pinfunction "GND_64") (pintype "bidirectional"))
      (node (ref "U4") (pin "4") (pinfunction "GND_4") (pintype "bidirectional"))
      (node (ref "U5") (pin "11") (pinfunction "PAD_11") (pintype "power_in"))
      (node (ref "U5") (pin "12") (pinfunction "PAD_12") (pintype "power_in"))
      (node (ref "U5") (pin "13") (pinfunction "PAD_13") (pintype "power_in"))
      (node (ref "U5") (pin "14") (pinfunction "PAD_14") (pintype "power_in"))
      (node (ref "U5") (pin "15") (pinfunction "PAD_15") (pintype "power_in"))
      (node (ref "U5") (pin "4") (pinfunction "PGND_4") (pintype "power_in"))
      (node (ref "U5") (pin "9") (pinfunction "GND_9") (pintype "power_in"))
      (node (ref "U6") (pin "2") (pinfunction "GND_2") (pintype "bidirectional"))
      (node (ref "U6") (pin "3") (pinfunction "GND_3") (pintype "bidirectional"))
      (node (ref "U6") (pin "4") (pinfunction "GND_4") (pintype "bidirectional"))
      (node (ref "U6") (pin "5") (pinfunction "GND_5") (pintype "bidirectional"))
      (node (ref "U6") (pin "6") (pinfunction "GND_6") (pintype "bidirectional"))
      (node (ref "U7") (pin "2") (pinfunction "ADDR_2") (pintype "input"))
      (node (ref "U7") (pin "3") (pinfunction "GND_3") (pintype "power_in"))
      (node (ref "U9") (pin "3") (pinfunction "GND_3") (pintype "power_in"))
      (node (ref "Y1") (pin "2") (pinfunction "2_2") (pintype "passive"))
    )
    (net (code "34") (name "GND-ISO") (class "Default")
      (node (ref "C4") (pin "1") (pinfunction "1_1") (pintype "passive"))
      (node (ref "J2") (pin "P$1") (pinfunction "GND_P$1") (pintype "bidirectional"))
      (node (ref "J2") (pin "P$2") (pinfunction "GND_P$2") (pintype "bidirectional"))
      (node (ref "PT1") (pin "P$2") (pinfunction "P$2_P$2") (pintype "bidirectional"))
      (node (ref "U$52") (pin "P$1") (pinfunction "P$1_P$1") (pintype "bidirectional"))
      (node (ref "U$52") (pin "P$2") (pinfunction "P$1_P$2") (pintype "bidirectional"))
      (node (ref "U$52") (pin "P$3") (pinfunction "P$1_P$3") (pintype "bidirectional"))
      (node (ref "U$52") (pin "P$4") (pinfunction "P$1_P$4") (pintype "bidirectional"))
      (node (ref "U$52") (pin "P$5") (pinfunction "P$1_P$5") (pintype "bidirectional"))
      (node (ref "U$52") (pin "P$6") (pinfunction "P$1_P$6") (pintype "bidirectional"))
      (node (ref "U$52") (pin "P$7") (pinfunction "P$1_P$7") (pintype "bidirectional"))
      (node (ref "U$52") (pin "P$8") (pinfunction "P$1_P$8") (pintype "bidirectional"))
      (node (ref "U$52") (pin "P$9") (pinfunction "P$1_P$9") (pintype "bidirectional"))
      (node (ref "U3") (pin "21") (pinfunction "GNDRF_21") (pintype "bidirectional"))
      (node (ref "U3") (pin "22") (pinfunction "GNDRF_22") (pintype "bidirectional"))
      (node (ref "U3") (pin "24") (pinfunction "GNDRF_24") (pintype "bidirectional"))
      (node (ref "U3") (pin "25") (pinfunction "GNDRF_25") (pintype "bidirectional"))
      (node (ref "U3") (pin "27") (pinfunction "GNDRF_27") (pintype "bidirectional"))
      (node (ref "U3") (pin "28") (pinfunction "GNDRF_28") (pintype "bidirectional"))
      (node (ref "U3") (pin "29") (pinfunction "GNDRF_29") (pintype "bidirectional"))
      (node (ref "U3") (pin "31") (pinfunction "GNDRF_31") (pintype "bidirectional"))
      (node (ref "U3") (pin "33") (pinfunction "GNDRF_33") (pintype "bidirectional"))
      (node (ref "U3") (pin "61") (pinfunction "GNDRF_61") (pintype "bidirectional"))
      (node (ref "U3") (pin "62") (pinfunction "GNDRF_62") (pintype "bidirectional"))
      (node (ref "U3") (pin "65") (pinfunction "GNDRF_65") (pintype "bidirectional"))
      (node (ref "U3") (pin "69") (pinfunction "GNDRF_69") (pintype "bidirectional"))
    )
    (net (code "35") (name "GND-ISO-2") (class "Default")
      (node (ref "C35") (pin "2") (pinfunction "2_2") (pintype "passive"))
      (node (ref "C48") (pin "1") (pinfunction "1_1") (pintype "passive"))
      (node (ref "C49") (pin "2") (pinfunction "2_2") (pintype "passive"))
      (node (ref "C50") (pin "1") (pinfunction "1_1") (pintype "passive"))
      (node (ref "C55") (pin "2") (pinfunction "2_2") (pintype "passive"))
      (node (ref "C59") (pin "1") (pinfunction "1_1") (pintype "passive"))
      (node (ref "C61") (pin "2") (pinfunction "2_2") (pintype "passive"))
      (node (ref "C62") (pin "2") (pinfunction "2_2") (pintype "passive"))
      (node (ref "C63") (pin "2") (pinfunction "2_2") (pintype "passive"))
      (node (ref "C64") (pin "2") (pinfunction "2_2") (pintype "passive"))
      (node (ref "C65") (pin "2") (pinfunction "2_2") (pintype "passive"))
      (node (ref "C66") (pin "2") (pinfunction "2_2") (pintype "passive"))
      (node (ref "SJ1") (pin "1") (pinfunction "1_1") (pintype "passive"))
      (node (ref "U$11") (pin "1") (pinfunction "GND_A_1") (pintype "bidirectional"))
      (node (ref "U$11") (pin "10") (pinfunction "OFFSET-B_10") (pintype "bidirectional"))
      (node (ref "U$11") (pin "13") (pinfunction "GND2_B_13") (pintype "bidirectional"))
      (node (ref "U$11") (pin "14") (pinfunction "S/R+B_14") (pintype "bidirectional"))
      (node (ref "U$11") (pin "16") (pinfunction "S/R+A_16") (pintype "bidirectional"))
      (node (ref "U$11") (pin "18") (pinfunction "GND_P_18") (pintype "bidirectional"))
      (node (ref "U$11") (pin "3") (pinfunction "OFFSET-A_3") (pintype "bidirectional"))
      (node (ref "U$11") (pin "6") (pinfunction "GND2_A_6") (pintype "bidirectional"))
      (node (ref "U$11") (pin "8") (pinfunction "GND1_B_8") (pintype "bidirectional"))
      (node (ref "U$12") (pin "P$1") (pinfunction "S/R+_P$1") (pintype "bidirectional"))
      (node (ref "U$12") (pin "P$2") (pinfunction "OFFSET+_P$2") (pintype "bidirectional"))
      (node (ref "U$12") (pin "P$4") (pinfunction "GND_P$4") (pintype "bidirectional"))
      (node (ref "U$12") (pin "P$6") (pinfunction "OFFSET-_P$6") (pintype "bidirectional"))
      (node (ref "U$17") (pin "P$1") (pinfunction "S1_P$1") (pintype "bidirectional"))
      (node (ref "U$22") (pin "4") (pinfunction "GND_4") (pintype "bidirectional"))
      (node (ref "U$7") (pin "10") (pinfunction "VREFCOM_10") (pintype "bidirectional"))
      (node (ref "U$7") (pin "21") (pinfunction "AVSS_21") (pintype "bidirectional"))
      (node (ref "U$7") (pin "6") (pinfunction "REFN0_6") (pintype "bidirectional"))
      (node (ref "U$7") (pin "8") (pinfunction "REFN1_8") (pintype "bidirectional"))
    )
    (net (code "36") (name "GPSEN") (class "Default")
      (node (ref "T1") (pin "3") (pinfunction "G_3") (pintype "passive"))
      (node (ref "U1") (pin "24") (pinfunction "(OC1A/PCINT5)PB5_24") (pintype "bidirectional"))
    )
    (net (code "37") (name "INHIBIT_ENABLE") (class "Default")
      (node (ref "C36") (pin "1") (pinfunction "1_1") (pintype "passive"))
      (node (ref "C37") (pin "1") (pinfunction "1_1") (pintype "passive"))
      (node (ref "C38") (pin "1") (pinfunction "1_1") (pintype "passive"))
      (node (ref "C39") (pin "1") (pinfunction "1_1") (pintype "passive"))
      (node (ref "C40") (pin "1") (pinfunction "1_1") (pintype "passive"))
      (node (ref "C41") (pin "1") (pinfunction "1_1") (pintype "passive"))
      (node (ref "C42") (pin "1") (pinfunction "1_1") (pintype "passive"))
      (node (ref "R39") (pin "2") (pinfunction "2_2") (pintype "passive"))
      (node (ref "S3") (pin "NC") (pinfunction "NC_NC") (pintype "passive"))
      (node (ref "U$13") (pin "2") (pinfunction "VS_2") (pintype "bidirectional"))
      (node (ref "U$13") (pin "4") (pinfunction "CTL_4") (pintype "bidirectional"))
      (node (ref "U$14") (pin "2") (pinfunction "VS_2") (pintype "bidirectional"))
      (node (ref "U$14") (pin "4") (pinfunction "CTL_4") (pintype "bidirectional"))
      (node (ref "U$15") (pin "2") (pinfunction "VS_2") (pintype "bidirectional"))
      (node (ref "U$15") (pin "4") (pinfunction "CTL_4") (pintype "bidirectional"))
      (node (ref "U$16") (pin "2") (pinfunction "VS_2") (pintype "bidirectional"))
      (node (ref "U$16") (pin "4") (pinfunction "CTL_4") (pintype "bidirectional"))
      (node (ref "U$19") (pin "2") (pinfunction "VS_2") (pintype "bidirectional"))
      (node (ref "U$19") (pin "4") (pinfunction "CTL_4") (pintype "bidirectional"))
      (node (ref "U$20") (pin "2") (pinfunction "VS_2") (pintype "bidirectional"))
      (node (ref "U$20") (pin "4") (pinfunction "CTL_4") (pintype "bidirectional"))
      (node (ref "U$8") (pin "2") (pinfunction "VS_2") (pintype "bidirectional"))
      (node (ref "U$8") (pin "4") (pinfunction "CTL_4") (pintype "bidirectional"))
    )
    (net (code "38") (name "INTERRUPT") (class "Default")
      (node (ref "U$3") (pin "14") (pinfunction "NIRQ_14") (pintype "output"))
      (node (ref "U1") (pin "6") (pinfunction "(OC3B/INT4)PE4_6") (pintype "bidirectional"))
    )
    (net (code "39") (name "LDAC") (class "Default")
      (node (ref "U1") (pin "23") (pinfunction "(OC2A/PCINT4)PB4_23") (pintype "bidirectional"))
    )
    (net (code "40") (name "LM_OUTPUT") (class "Default")
      (node (ref "C13") (pin "1") (pinfunction "1_1") (pintype "passive"))
      (node (ref "C14") (pin "1") (pinfunction "1_1") (pintype "passive"))
      (node (ref "C8") (pin "1") (pinfunction "1_1") (pintype "passive"))
      (node (ref "C9") (pin "1") (pinfunction "1_1") (pintype "passive"))
      (node (ref "D1") (pin "C") (pinfunction "C_C") (pintype "passive"))
      (node (ref "R18") (pin "2") (pinfunction "2_2") (pintype "passive"))
      (node (ref "R26") (pin "1") (pinfunction "1_1") (pintype "passive"))
    )
    (net (code "41") (name "LM_SW") (class "Default")
      (node (ref "D1") (pin "A") (pinfunction "A_A") (pintype "passive"))
      (node (ref "L7") (pin "2") (pinfunction "2_2") (pintype "passive"))
      (node (ref "U$4") (pin "1") (pinfunction "SW_1") (pintype "bidirectional"))
    )
    (net (code "42") (name "LM_VIN") (class "Default")
      (node (ref "C17") (pin "1") (pinfunction "1_1") (pintype "passive"))
      (node (ref "C18") (pin "1") (pinfunction "1_1") (pintype "passive"))
      (node (ref "C43") (pin "A") (pinfunction "+_A") (pintype "passive"))
      (node (ref "L7") (pin "1") (pinfunction "1_1") (pintype "passive"))
      (node (ref "R9") (pin "2") (pinfunction "2_2") (pintype "passive"))
      (node (ref "U$4") (pin "5") (pinfunction "VIN_5") (pintype "bidirectional"))
    )
    (net (code "43") (name "LSPS_ISL") (class "Default")
      (node (ref "U1") (pin "5") (pinfunction "(OC3A/AIN1)PE3_5") (pintype "bidirectional"))
    )
    (net (code "44") (name "MISO") (class "Default")
      (node (ref "R64") (pin "2") (pinfunction "2_2") (pintype "passive"))
      (node (ref "U$3") (pin "10") (pinfunction "SDO_10") (pintype "output"))
      (node (ref "U$50") (pin "4") (pinfunction "4_4") (pintype "bidirectional"))
      (node (ref "U1") (pin "22") (pinfunction "(MISO/PCINT3)PB3_22") (pintype "bidirectional"))
      (node (ref "U2") (pin "DO") (pinfunction "DO_DO") (pintype "bidirectional"))
    )
    (net (code "45") (name "MOSI_3.3") (class "Default")
      (node (ref "U$1") (pin "2") (pinfunction "1Y_2") (pintype "bidirectional"))
      (node (ref "U$3") (pin "11") (pinfunction "SDI_11") (pintype "input"))
      (node (ref "U2") (pin "DI") (pinfunction "DI_DI") (pintype "bidirectional"))
    )
    (net (code "46") (name "MOSI_5.0") (class "Default")
      (node (ref "R63") (pin "2") (pinfunction "2_2") (pintype "passive"))
      (node (ref "U$1") (pin "3") (pinfunction "1A_3") (pintype "bidirectional"))
      (node (ref "U$50") (pin "5") (pinfunction "5_5") (pintype "bidirectional"))
      (node (ref "U1") (pin "21") (pinfunction "(MOSI/PCINT2)PB2_21") (pintype "bidirectional"))
    )
    (net (code "47") (name "N$27") (class "Default")
      (node (ref "C19") (pin "1") (pinfunction "1_1") (pintype "passive"))
      (node (ref "C60") (pin "1") (pinfunction "1_1") (pintype "passive"))
      (node (ref "R27") (pin "1") (pinfunction "1_1") (pintype "passive"))
      (node (ref "U$6") (pin "1") (pinfunction "VOUT_1") (pintype "bidirectional"))
    )
    (net (code "48") (name "N$34") (class "Default")
      (node (ref "L3") (pin "1") (pinfunction "1_1") (pintype "passive"))
      (node (ref "R27") (pin "2") (pinfunction "2_2") (pintype "passive"))
      (node (ref "U1") (pin "85") (pinfunction "PK4(ADC12/PCINT20)_85") (pintype "bidirectional"))
    )
    (net (code "49") (name "N$54") (class "Default")
      (node (ref "Q2") (pin "S1") (pinfunction "S_S1") (pintype "passive"))
      (node (ref "Q2") (pin "S2") (pinfunction "S_S2") (pintype "passive"))
      (node (ref "Q2") (pin "S3") (pinfunction "S_S3") (pintype "passive"))
      (node (ref "Q4") (pin "D1") (pinfunction "D_D1") (pintype "passive"))
      (node (ref "Q4") (pin "D2") (pinfunction "D_D2") (pintype "passive"))
      (node (ref "Q4") (pin "D3") (pinfunction "D_D3") (pintype "passive"))
      (node (ref "Q4") (pin "D4") (pinfunction "D_D4") (pintype "passive"))
      (node (ref "Q4") (pin "DPAD") (pinfunction "D_DPAD") (pintype "passive"))
    )
    (net (code "50") (name "N$55") (class "Default")
      (node (ref "Q1") (pin "S1") (pinfunction "S_S1") (pintype "passive"))
      (node (ref "Q1") (pin "S2") (pinfunction "S_S2") (pintype "passive"))
      (node (ref "Q1") (pin "S3") (pinfunction "S_S3") (pintype "passive"))
      (node (ref "Q2") (pin "D1") (pinfunction "D_D1") (pintype "passive"))
      (node (ref "Q2") (pin "D2") (pinfunction "D_D2") (pintype "passive"))
      (node (ref "Q2") (pin "D3") (pinfunction "D_D3") (pintype "passive"))
      (node (ref "Q2") (pin "D4") (pinfunction "D_D4") (pintype "passive"))
      (node (ref "Q2") (pin "DPAD") (pinfunction "D_DPAD") (pintype "passive"))
    )
    (net (code "51") (name "N$62") (class "Default")
      (node (ref "Q5") (pin "S1") (pinfunction "S_S1") (pintype "passive"))
      (node (ref "Q5") (pin "S2") (pinfunction "S_S2") (pintype "passive"))
      (node (ref "Q5") (pin "S3") (pinfunction "S_S3") (pintype "passive"))
      (node (ref "Q6") (pin "D1") (pinfunction "D_D1") (pintype "passive"))
      (node (ref "Q6") (pin "D2") (pinfunction "D_D2") (pintype "passive"))
      (node (ref "Q6") (pin "D3") (pinfunction "D_D3") (pintype "passive"))
      (node (ref "Q6") (pin "D4") (pinfunction "D_D4") (pintype "passive"))
      (node (ref "Q6") (pin "DPAD") (pinfunction "D_DPAD") (pintype "passive"))
    )
    (net (code "52") (name "N$63") (class "Default")
      (node (ref "Q6") (pin "S1") (pinfunction "S_S1") (pintype "passive"))
      (node (ref "Q6") (pin "S2") (pinfunction "S_S2") (pintype "passive"))
      (node (ref "Q6") (pin "S3") (pinfunction "S_S3") (pintype "passive"))
      (node (ref "Q7") (pin "D1") (pinfunction "D_D1") (pintype "passive"))
      (node (ref "Q7") (pin "D2") (pinfunction "D_D2") (pintype "passive"))
      (node (ref "Q7") (pin "D3") (pinfunction "D_D3") (pintype "passive"))
      (node (ref "Q7") (pin "D4") (pinfunction "D_D4") (pintype "passive"))
      (node (ref "Q7") (pin "DPAD") (pinfunction "D_DPAD") (pintype "passive"))
    )
    (net (code "53") (name "N$113") (class "Default")
      (node (ref "C15") (pin "1") (pinfunction "1_1") (pintype "passive"))
      (node (ref "C16") (pin "1") (pinfunction "1_1") (pintype "passive"))
      (node (ref "L2") (pin "2") (pinfunction "2_2") (pintype "passive"))
      (node (ref "R28") (pin "1") (pinfunction "1_1") (pintype "passive"))
    )
    (net (code "54") (name "Net-(C33-Pad2)") (class "Default")
      (node (ref "C33") (pin "2") (pinfunction "2_2") (pintype "passive"))
      (node (ref "C34") (pin "2") (pinfunction "2_2") (pintype "passive"))
      (node (ref "U$17") (pin "P$5") (pinfunction "D2_P$5") (pintype "bidirectional"))
      (node (ref "U$17") (pin "P$6") (pinfunction "D2_P$6") (pintype "bidirectional"))
      (node (ref "U$17") (pin "P$7") (pinfunction "D1_P$7") (pintype "bidirectional"))
      (node (ref "U$17") (pin "P$8") (pinfunction "D1_P$8") (pintype "bidirectional"))
    )
    (net (code "55") (name "Net-(C54-Pad1)") (class "Default")
      (node (ref "C54") (pin "1") (pinfunction "1_1") (pintype "passive"))
      (node (ref "L6") (pin "2") (pinfunction "2_2") (pintype "passive"))
      (node (ref "U$23") (pin "P$1") (pinfunction "P$1_P$1") (pintype "bidirectional"))
    )
    (net (code "56") (name "Net-(D2-PadC)") (class "Default")
      (node (ref "D2") (pin "C") (pinfunction "C_C") (pintype "passive"))
      (node (ref "R83") (pin "2") (pinfunction "2_2") (pintype "passive"))
    )
    (net (code "57") (name "Net-(D3-PadC)") (class "Default")
      (node (ref "D3") (pin "C") (pinfunction "C_C") (pintype "passive"))
      (node (ref "R84") (pin "2") (pinfunction "2_2") (pintype "passive"))
    )
    (net (code "58") (name "Net-(D4-PadA)") (class "Default")
      (node (ref "D4") (pin "A") (pinfunction "A_A") (pintype "passive"))
      (node (ref "R44") (pin "2") (pinfunction "2_2") (pintype "passive"))
    )
    (net (code "59") (name "Net-(D5-PadA)") (class "Default")
      (node (ref "D5") (pin "A") (pinfunction "A_A") (pintype "passive"))
      (node (ref "R45") (pin "2") (pinfunction "2_2") (pintype "passive"))
    )
    (net (code "60") (name "Net-(J2-SIGNAL)") (class "Default")
      (node (ref "J2") (pin "P$3") (pinfunction "SIGNAL_P$3") (pintype "bidirectional"))
      (node (ref "L1") (pin "1") (pinfunction "1_1") (pintype "passive"))
      (node (ref "U3") (pin "32") (pinfunction "RFIN_32") (pintype "bidirectional"))
    )
    (net (code "61") (name "Net-(J4-1)") (class "Default")
      (node (ref "J4") (pin "P$1") (pinfunction "1_P$1") (pintype "passive"))
      (node (ref "U1") (pin "74") (pinfunction "(AD4)PA4_74") (pintype "bidirectional"))
    )
    (net (code "62") (name "Net-(J4-2)") (class "Default")
      (node (ref "J4") (pin "P$2") (pinfunction "2_P$2") (pintype "passive"))
      (node (ref "U1") (pin "75") (pinfunction "(AD3)PA3_75") (pintype "bidirectional"))
    )
    (net (code "63") (name "Net-(LED1-PadA)") (class "Default")
      (node (ref "LED1") (pin "A") (pinfunction "A_A") (pintype "passive"))
      (node (ref "R14") (pin "1") (pinfunction "1_1") (pintype "passive"))
    )
    (net (code "64") (name "Net-(LED1-PadC)") (class "Default")
      (node (ref "LED1") (pin "C") (pinfunction "C_C") (pintype "passive"))
      (node (ref "R60") (pin "1") (pinfunction "1_1") (pintype "passive"))
    )
    (net (code "65") (name "Net-(LED2-PadC)") (class "Default")
      (node (ref "LED2") (pin "C") (pinfunction "C_C") (pintype "passive"))
      (node (ref "R15") (pin "2") (pinfunction "2_2") (pintype "passive"))
    )
    (net (code "66") (name "Net-(LED7-PadC)") (class "Default")
      (node (ref "LED7") (pin "C") (pinfunction "C_C") (pintype "passive"))
      (node (ref "R40") (pin "2") (pinfunction "2_2") (pintype "passive"))
    )
    (net (code "67") (name "Net-(LED8-PadC)") (class "Default")
      (node (ref "LED8") (pin "C") (pinfunction "C_C") (pintype "passive"))
      (node (ref "R41") (pin "1") (pinfunction "1_1") (pintype "passive"))
    )
    (net (code "68") (name "Net-(LED9-PadC)") (class "Default")
      (node (ref "LED9") (pin "C") (pinfunction "C_C") (pintype "passive"))
      (node (ref "R43") (pin "2") (pinfunction "2_2") (pintype "passive"))
    )
    (net (code "69") (name "Net-(LED10-PadC)") (class "Default")
      (node (ref "LED10") (pin "C") (pinfunction "C_C") (pintype "passive"))
      (node (ref "R42") (pin "2") (pinfunction "2_2") (pintype "passive"))
    )
    (net (code "70") (name "Net-(Q9-G)") (class "Default")
      (node (ref "Q9") (pin "1") (pinfunction "G_1") (pintype "passive"))
      (node (ref "U$27") (pin "5") (pinfunction "CO_5") (pintype "bidirectional"))
    )
    (net (code "71") (name "Net-(Q11-D)") (class "Default")
      (node (ref "Q11") (pin "3") (pinfunction "D_3") (pintype "passive"))
      (node (ref "Q9") (pin "3") (pinfunction "D_3") (pintype "passive"))
    )
    (net (code "72") (name "Net-(Q11-G)") (class "Default")
      (node (ref "Q11") (pin "1") (pinfunction "G_1") (pintype "passive"))
      (node (ref "U$27") (pin "4") (pinfunction "DO_4") (pintype "bidirectional"))
    )
    (net (code "73") (name "Net-(S1-PadNC)") (class "Default")
      (node (ref "S1") (pin "NC") (pinfunction "NC_NC") (pintype "passive"))
      (node (ref "S2") (pin "COM") (pinfunction "COM_COM") (pintype "passive"))
    )
    (net (code "74") (name "Net-(S2-PadNC)") (class "Default")
      (node (ref "S2") (pin "NC") (pinfunction "NC_NC") (pintype "passive"))
      (node (ref "S3") (pin "COM") (pinfunction "COM_COM") (pintype "passive"))
    )
    (net (code "75") (name "Net-(U$3-ANT)") (class "Default")
      (node (ref "L6") (pin "1") (pinfunction "1_1") (pintype "passive"))
      (node (ref "U$3") (pin "1") (pinfunction "ANT_1") (pintype "bidirectional"))
    )
    (net (code "76") (name "Net-(U$3-GPIO0)") (class "Default")
      (node (ref "U$3") (pin "4") (pinfunction "TXANT_4") (pintype "input"))
      (node (ref "U$3") (pin "6") (pinfunction "GPIO0_6") (pintype "bidirectional"))
    )
    (net (code "77") (name "Net-(U$3-GPIO1)") (class "Default")
      (node (ref "U$3") (pin "3") (pinfunction "RXANT_3") (pintype "input"))
      (node (ref "U$3") (pin "7") (pinfunction "GPIO1_7") (pintype "bidirectional"))
    )
    (net (code "78") (name "Net-(U$7-CS)") (class "Default")
      (node (ref "R67") (pin "1") (pinfunction "1_1") (pintype "passive"))
      (node (ref "U$7") (pin "24") (pinfunction "CS_24") (pintype "bidirectional"))
    )
    (net (code "79") (name "Net-(U$7-DIN)") (class "Default")
      (node (ref "R63") (pin "1") (pinfunction "1_1") (pintype "passive"))
      (node (ref "U$7") (pin "27") (pinfunction "DIN_27") (pintype "bidirectional"))
    )
    (net (code "80") (name "Net-(U$7-DOUT{slash}DRDY)") (class "Default")
      (node (ref "R64") (pin "1") (pinfunction "1_1") (pintype "passive"))
      (node (ref "U$7") (pin "26") (pinfunction "DOUT/DRDY_26") (pintype "bidirectional"))
    )
    (net (code "81") (name "Net-(U$7-DRDY)") (class "Default")
      (node (ref "R66") (pin "1") (pinfunction "1_1") (pintype "passive"))
      (node (ref "U$7") (pin "25") (pinfunction "DRDY_25") (pintype "bidirectional"))
    )
    (net (code "82") (name "Net-(U$7-RESET)") (class "Default")
      (node (ref "R56") (pin "1") (pinfunction "1_1") (pintype "passive"))
      (node (ref "U$7") (pin "4") (pinfunction "RESET_4") (pintype "bidirectional"))
    )
    (net (code "83") (name "Net-(U$7-SCLK)") (class "Default")
      (node (ref "R52") (pin "1") (pinfunction "1_1") (pintype "passive"))
      (node (ref "U$7") (pin "28") (pinfunction "SCLK_28") (pintype "bidirectional"))
    )
    (net (code "84") (name "Net-(U$7-START)") (class "Default")
      (node (ref "R82") (pin "1") (pinfunction "1_1") (pintype "passive"))
      (node (ref "U$7") (pin "23") (pinfunction "START_23") (pintype "bidirectional"))
    )
    (net (code "85") (name "Net-(U$7-VREFOUT)") (class "Default")
      (node (ref "C50") (pin "2") (pinfunction "2_2") (pintype "passive"))
      (node (ref "U$7") (pin "9") (pinfunction "VREFOUT_9") (pintype "bidirectional"))
    )
    (net (code "86") (name "Net-(U$8-G)") (class "Default")
      (node (ref "Q1") (pin "G") (pinfunction "G_G") (pintype "passive"))
      (node (ref "R20") (pin "2") (pinfunction "2_2") (pintype "passive"))
      (node (ref "U$8") (pin "3") (pinfunction "G_3") (pintype "bidirectional"))
    )
    (net (code "87") (name "Net-(U$13-G)") (class "Default")
      (node (ref "Q2") (pin "G") (pinfunction "G_G") (pintype "passive"))
      (node (ref "R24") (pin "2") (pinfunction "2_2") (pintype "passive"))
      (node (ref "U$13") (pin "3") (pinfunction "G_3") (pintype "bidirectional"))
    )
    (net (code "88") (name "Net-(U$14-G)") (class "Default")
      (node (ref "Q4") (pin "G") (pinfunction "G_G") (pintype "passive"))
      (node (ref "R29") (pin "2") (pinfunction "2_2") (pintype "passive"))
      (node (ref "U$14") (pin "3") (pinfunction "G_3") (pintype "bidirectional"))
    )
    (net (code "89") (name "Net-(U$15-G)") (class "Default")
      (node (ref "Q5") (pin "G") (pinfunction "G_G") (pintype "passive"))
      (node (ref "R33") (pin "2") (pinfunction "2_2") (pintype "passive"))
      (node (ref "U$15") (pin "3") (pinfunction "G_3") (pintype "bidirectional"))
    )
    (net (code "90") (name "Net-(U$16-G)") (class "Default")
      (node (ref "Q6") (pin "G") (pinfunction "G_G") (pintype "passive"))
      (node (ref "R35") (pin "2") (pinfunction "2_2") (pintype "passive"))
      (node (ref "U$16") (pin "3") (pinfunction "G_3") (pintype "bidirectional"))
    )
    (net (code "91") (name "Net-(U$17-S2)") (class "Default")
      (node (ref "C35") (pin "1") (pinfunction "1_1") (pintype "passive"))
      (node (ref "R57") (pin "2") (pinfunction "2_2") (pintype "passive"))
      (node (ref "U$17") (pin "P$3") (pinfunction "S2_P$3") (pintype "bidirectional"))
    )
    (net (code "92") (name "Net-(U$19-G)") (class "Default")
      (node (ref "Q7") (pin "G") (pinfunction "G_G") (pintype "passive"))
      (node (ref "R37") (pin "2") (pinfunction "2_2") (pintype "passive"))
      (node (ref "U$19") (pin "3") (pinfunction "G_3") (pintype "bidirectional"))
    )
    (net (code "93") (name "Net-(U$20-G)") (class "Default")
      (node (ref "Q8") (pin "G") (pinfunction "G_G") (pintype "passive"))
      (node (ref "R38") (pin "2") (pinfunction "2_2") (pintype "passive"))
      (node (ref "U$20") (pin "3") (pinfunction "G_3") (pintype "bidirectional"))
    )
    (net (code "94") (name "Net-(U$27-VDD)") (class "Default")
      (node (ref "C51") (pin "1") (pinfunction "1_1") (pintype "passive"))
      (node (ref "R54") (pin "2") (pinfunction "2_2") (pintype "passive"))
      (node (ref "U$27") (pin "2") (pinfunction "VDD_2") (pintype "bidirectional"))
    )
    (net (code "95") (name "Net-(U$27-VM)") (class "Default")
      (node (ref "R55") (pin "2") (pinfunction "2_2") (pintype "passive"))
      (node (ref "U$27") (pin "1") (pinfunction "VM_1") (pintype "bidirectional"))
    )
    (net (code "96") (name "Net-(U1-(OC0A{slash}OC1C{slash}PCINT7)PB7)") (class "Default")
      (node (ref "LED2") (pin "A") (pinfunction "A_A") (pintype "passive"))
      (node (ref "U1") (pin "26") (pinfunction "(OC0A/OC1C/PCINT7)PB7_26") (pintype "bidirectional"))
    )
    (net (code "97") (name "Net-(U1-(OC1B{slash}PCINT6)PB6)") (class "Default")
      (node (ref "LED7") (pin "A") (pinfunction "A_A") (pintype "passive"))
      (node (ref "U1") (pin "25") (pinfunction "(OC1B/PCINT6)PB6_25") (pintype "bidirectional"))
    )
    (net (code "98") (name "Net-(U1-(TOSC1)PG4)") (class "Default")
      (node (ref "LED10") (pin "A") (pinfunction "A_A") (pintype "passive"))
      (node (ref "U1") (pin "29") (pinfunction "(TOSC1)PG4_29") (pintype "bidirectional"))
    )
    (net (code "99") (name "Net-(U1-(TOSC2)PG3)") (class "Default")
      (node (ref "LED9") (pin "A") (pinfunction "A_A") (pintype "passive"))
      (node (ref "U1") (pin "28") (pinfunction "(TOSC2)PG3_28") (pintype "bidirectional"))
    )
    (net (code "100") (name "Net-(U1-PH7(T4))") (class "Default")
      (node (ref "LED8") (pin "A") (pinfunction "A_A") (pintype "passive"))
      (node (ref "U1") (pin "27") (pinfunction "PH7(T4)_27") (pintype "bidirectional"))
    )
    (net (code "101") (name "Net-(U1-XTAL1)") (class "Default")
      (node (ref "R1") (pin "1") (pinfunction "1_1") (pintype "passive"))
      (node (ref "U1") (pin "34") (pinfunction "XTAL1_34") (pintype "input"))
      (node (ref "Y1") (pin "3") (pinfunction "3_3") (pintype "passive"))
    )
    (net (code "102") (name "Net-(U1-XTAL2)") (class "Default")
      (node (ref "R1") (pin "2") (pinfunction "2_2") (pintype "passive"))
      (node (ref "U1") (pin "33") (pinfunction "XTAL2_33") (pintype "output"))
      (node (ref "Y1") (pin "1") (pinfunction "1_1") (pintype "passive"))
    )
    (net (code "103") (name "Net-(U3-BTSEL)") (class "Default")
      (node (ref "C5") (pin "2") (pinfunction "2_2") (pintype "passive"))
      (node (ref "R10") (pin "1") (pinfunction "1_1") (pintype "passive"))
      (node (ref "U3") (pin "1") (pinfunction "RSTN_1") (pintype "bidirectional"))
      (node (ref "U3") (pin "9") (pinfunction "BTSEL_9") (pintype "bidirectional"))
    )
    (net (code "104") (name "Net-(U3-LED{slash}GPIO0)") (class "Default")
      (node (ref "R60") (pin "2") (pinfunction "2_2") (pintype "passive"))
      (node (ref "U3") (pin "7") (pinfunction "LED/GPIO0_7") (pintype "bidirectional"))
    )
    (net (code "105") (name "Net-(U4-EN)") (class "Default")
      (node (ref "C10") (pin "2") (pinfunction "2_2") (pintype "passive"))
      (node (ref "R6") (pin "1") (pinfunction "1_1") (pintype "passive"))
      (node (ref "U4") (pin "7") (pinfunction "VREF2_7") (pintype "bidirectional"))
      (node (ref "U4") (pin "8") (pinfunction "EN_8") (pintype "bidirectional"))
    )
    (net (code "106") (name "Net-(U5-L)") (class "Default")
      (node (ref "L4") (pin "2") (pinfunction "2_2") (pintype "passive"))
      (node (ref "U5") (pin "3") (pinfunction "L_3") (pintype "passive"))
    )
    (net (code "107") (name "Net-(U5-UVLO)") (class "Default")
      (node (ref "R30") (pin "1") (pinfunction "1_1") (pintype "passive"))
      (node (ref "R31") (pin "2") (pinfunction "2_2") (pintype "passive"))
      (node (ref "U5") (pin "7") (pinfunction "UVLO_7") (pintype "passive"))
    )
    (net (code "108") (name "Net-(U5-VAUX)") (class "Default")
      (node (ref "C23") (pin "1") (pinfunction "1_1") (pintype "passive"))
      (node (ref "U5") (pin "1") (pinfunction "VAUX_1") (pintype "passive"))
    )
    (net (code "109") (name "Net-(U6-C1)") (class "Default")
      (node (ref "C12") (pin "2") (pinfunction "2_2") (pintype "passive"))
      (node (ref "U6") (pin "7") (pinfunction "C1_7") (pintype "bidirectional"))
    )
    (net (code "110") (name "Net-(U6-CS(G))") (class "Default")
      (node (ref "R13") (pin "1") (pinfunction "1_1") (pintype "passive"))
      (node (ref "U6") (pin "19") (pinfunction "CS(G)_19") (pintype "bidirectional"))
    )
    (net (code "111") (name "Net-(U6-CS(XM))") (class "Default")
      (node (ref "R11") (pin "1") (pinfunction "1_1") (pintype "passive"))
      (node (ref "U6") (pin "20") (pinfunction "CS(XM)_20") (pintype "bidirectional"))
    )
    (net (code "112") (name "Net-(U6-SDO(G))") (class "Default")
      (node (ref "R34") (pin "1") (pinfunction "1_1") (pintype "passive"))
      (node (ref "U6") (pin "22") (pinfunction "SDO(G)_22") (pintype "bidirectional"))
    )
    (net (code "113") (name "Net-(U6-SDO(XM))") (class "Default")
      (node (ref "R16") (pin "1") (pinfunction "1_1") (pintype "passive"))
      (node (ref "U6") (pin "23") (pinfunction "SDO(XM)_23") (pintype "bidirectional"))
    )
    (net (code "114") (name "Net-(U6-SETC)") (class "Default")
      (node (ref "C11") (pin "2") (pinfunction "2_2") (pintype "passive"))
      (node (ref "U6") (pin "8") (pinfunction "SETC_8") (pintype "bidirectional"))
    )
    (net (code "115") (name "Net-(U6-SETP)") (class "Default")
      (node (ref "C11") (pin "1") (pinfunction "1_1") (pintype "passive"))
      (node (ref "U6") (pin "9") (pinfunction "SETP_9") (pintype "bidirectional"))
    )
    (net (code "116") (name "Net-(U8-PROG)") (class "Default")
      (node (ref "R62") (pin "2") (pinfunction "2_2") (pintype "passive"))
      (node (ref "U8") (pin "5") (pinfunction "PROG_5") (pintype "input"))
    )
    (net (code "117") (name "Net-(U8-STAT)") (class "Default")
      (node (ref "R84") (pin "1") (pinfunction "1_1") (pintype "passive"))
      (node (ref "U8") (pin "1") (pinfunction "STAT_1") (pintype "output"))
    )
    (net (code "118") (name "Net-(U11-L)") (class "Default")
      (node (ref "L8") (pin "2") (pinfunction "2_2") (pintype "passive"))
      (node (ref "U11") (pin "3") (pinfunction "L_3") (pintype "passive"))
    )
    (net (code "119") (name "Net-(U11-VAUX)") (class "Default")
      (node (ref "C7") (pin "1") (pinfunction "1_1") (pintype "passive"))
      (node (ref "U11") (pin "1") (pinfunction "VAUX_1") (pintype "passive"))
    )
    (net (code "120") (name "PWDN_ISL") (class "Default")
      (node (ref "U1") (pin "12") (pinfunction "PH0(RXD2)_12") (pintype "bidirectional"))
    )
    (net (code "121") (name "RADIO_CS_3.3") (class "Default")
      (node (ref "U$1") (pin "6") (pinfunction "3Y_6") (pintype "bidirectional"))
      (node (ref "U$3") (pin "13") (pinfunction "NSEL_13") (pintype "input"))
    )
    (net (code "122") (name "RADIO_CS_5.0") (class "Default")
      (node (ref "U$1") (pin "7") (pinfunction "3A_7") (pintype "bidirectional"))
      (node (ref "U1") (pin "19") (pinfunction "(SS/PCINT0)PB0_19") (pintype "bidirectional"))
    )
    (net (code "123") (name "REF") (class "Default")
      (node (ref "C55") (pin "1") (pinfunction "1_1") (pintype "passive"))
      (node (ref "U$22") (pin "6") (pinfunction "VOUT_6") (pintype "bidirectional"))
      (node (ref "U$7") (pin "5") (pinfunction "REFP0_5") (pintype "bidirectional"))
    )
    (net (code "124") (name "RESET") (class "Default")
      (node (ref "U$50") (pin "7") (pinfunction "7_7") (pintype "bidirectional"))
      (node (ref "U1") (pin "30") (pinfunction "RESET_30") (pintype "input"))
    )
    (net (code "125") (name "RESET_ADS") (class "Default")
      (node (ref "R56") (pin "2") (pinfunction "2_2") (pintype "passive"))
      (node (ref "R58") (pin "2") (pinfunction "2_2") (pintype "passive"))
      (node (ref "U1") (pin "17") (pinfunction "PH5(OC4C)_17") (pintype "bidirectional"))
    )
    (net (code "126") (name "RX") (class "Default")
      (node (ref "U1") (pin "45") (pinfunction "(RXD1/INT2)PD2_45") (pintype "bidirectional"))
      (node (ref "U3") (pin "44") (pinfunction "TXD0_44") (pintype "bidirectional"))
    )
    (net (code "127") (name "RX0") (class "Default")
      (node (ref "U$50") (pin "10") (pinfunction "10_10") (pintype "bidirectional"))
      (node (ref "U1") (pin "2") (pinfunction "(RXD0/PCIN8)PE0_2") (pintype "bidirectional"))
    )
    (net (code "128") (name "SCK_3.3") (class "Default")
      (node (ref "U$1") (pin "4") (pinfunction "2Y_4") (pintype "bidirectional"))
      (node (ref "U$3") (pin "12") (pinfunction "SCLK_12") (pintype "input"))
      (node (ref "U2") (pin "SCLK") (pinfunction "SCK_SCLK") (pintype "bidirectional"))
    )
    (net (code "129") (name "SCK_5.0") (class "Default")
      (node (ref "R52") (pin "2") (pinfunction "2_2") (pintype "passive"))
      (node (ref "U$1") (pin "5") (pinfunction "2A_5") (pintype "bidirectional"))
      (node (ref "U$50") (pin "6") (pinfunction "6_6") (pintype "bidirectional"))
      (node (ref "U1") (pin "20") (pinfunction "(SCK/PCINT1)PB1_20") (pintype "bidirectional"))
    )
    (net (code "130") (name "SCL_3.3") (class "Default")
      (node (ref "R4") (pin "1") (pinfunction "1_1") (pintype "passive"))
      (node (ref "U4") (pin "2") (pinfunction "SCL1_2") (pintype "bidirectional"))
      (node (ref "U6") (pin "21") (pinfunction "SCL_21") (pintype "bidirectional"))
      (node (ref "U7") (pin "4") (pinfunction "SCL_4") (pintype "input"))
      (node (ref "U9") (pin "4") (pinfunction "SCL_4") (pintype "input"))
    )
    (net (code "131") (name "SCL_5.0") (class "Default")
      (node (ref "R7") (pin "1") (pinfunction "1_1") (pintype "passive"))
      (node (ref "U1") (pin "43") (pinfunction "(SCL/INT0)PD0_43") (pintype "bidirectional"))
      (node (ref "U4") (pin "6") (pinfunction "SCL2_6") (pintype "bidirectional"))
    )
    (net (code "132") (name "SDA_3.3") (class "Default")
      (node (ref "R5") (pin "1") (pinfunction "1_1") (pintype "passive"))
      (node (ref "U4") (pin "3") (pinfunction "SDA1_3") (pintype "bidirectional"))
      (node (ref "U6") (pin "24") (pinfunction "SDA_24") (pintype "bidirectional"))
      (node (ref "U7") (pin "6") (pinfunction "SDA_6") (pintype "bidirectional"))
      (node (ref "U9") (pin "6") (pinfunction "SDA_6") (pintype "bidirectional"))
    )
    (net (code "133") (name "SDA_5.0") (class "Default")
      (node (ref "R8") (pin "1") (pinfunction "1_1") (pintype "passive"))
      (node (ref "U1") (pin "44") (pinfunction "(SDA/INT1)PD1_44") (pintype "bidirectional"))
      (node (ref "U4") (pin "5") (pinfunction "SDA2_5") (pintype "bidirectional"))
    )
    (net (code "134") (name "SD_CS_3.3") (class "Default")
      (node (ref "U$1") (pin "12") (pinfunction "5Y_12") (pintype "bidirectional"))
      (node (ref "U2") (pin "CS") (pinfunction "CS_CS") (pintype "bidirectional"))
    )
    (net (code "135") (name "SD_CS_5.0") (class "Default")
      (node (ref "U$1") (pin "11") (pinfunction "5A_11") (pintype "bidirectional"))
      (node (ref "U1") (pin "18") (pinfunction "PH6(OC2B)_18") (pintype "bidirectional"))
    )
    (net (code "136") (name "SET") (class "Default")
      (node (ref "U$17") (pin "P$2") (pinfunction "G1_P$2") (pintype "bidirectional"))
      (node (ref "U$17") (pin "P$4") (pinfunction "G2_P$4") (pintype "bidirectional"))
      (node (ref "U1") (pin "97") (pinfunction "(ADC0)PF0_97") (pintype "bidirectional"))
    )
    (net (code "137") (name "SET{slash}RESET") (class "Default")
      (node (ref "C33") (pin "1") (pinfunction "1_1") (pintype "passive"))
      (node (ref "C34") (pin "1") (pinfunction "1_1") (pintype "passive"))
      (node (ref "U$11") (pin "20") (pinfunction "S/R-A_20") (pintype "bidirectional"))
      (node (ref "U$11") (pin "7") (pinfunction "S/R-B_7") (pintype "bidirectional"))
      (node (ref "U$12") (pin "P$3") (pinfunction "S/R-_P$3") (pintype "bidirectional"))
    )
    (net (code "138") (name "SHDN_3.3") (class "Default")
      (node (ref "R2") (pin "2") (pinfunction "2_2") (pintype "passive"))
      (node (ref "U$1") (pin "10") (pinfunction "4Y_10") (pintype "bidirectional"))
      (node (ref "U$3") (pin "15") (pinfunction "SDN_15") (pintype "input"))
    )
    (net (code "139") (name "SHDN_5.0") (class "Default")
      (node (ref "U$1") (pin "9") (pinfunction "4A_9") (pintype "bidirectional"))
      (node (ref "U1") (pin "1") (pinfunction "(OC0B)PG5_1") (pintype "bidirectional"))
    )
    (net (code "140") (name "SOLAR") (class "Default")
      (node (ref "J1") (pin "P$1") (pinfunction "1_P$1") (pintype "passive"))
      (node (ref "J3") (pin "P$1") (pinfunction "1_P$1") (pintype "passive"))
      (node (ref "Q1") (pin "D1") (pinfunction "D_D1") (pintype "passive"))
      (node (ref "Q1") (pin "D2") (pinfunction "D_D2") (pintype "passive"))
      (node (ref "Q1") (pin "D3") (pinfunction "D_D3") (pintype "passive"))
      (node (ref "Q1") (pin "D4") (pinfunction "D_D4") (pintype "passive"))
      (node (ref "Q1") (pin "DPAD") (pinfunction "D_DPAD") (pintype "passive"))
    )
    (net (code "141") (name "START_ADS") (class "Default")
      (node (ref "R82") (pin "2") (pinfunction "2_2") (pintype "passive"))
      (node (ref "U1") (pin "13") (pinfunction "PH1(TXD2)_13") (pintype "bidirectional"))
    )
    (net (code "143") (name "TEMP_SENSE") (class "Default")
      (node (ref "U$24") (pin "4") (pinfunction "DQ_4") (pintype "bidirectional"))
      (node (ref "U$25") (pin "4") (pinfunction "DQ_4") (pintype "bidirectional"))
      (node (ref "U$47") (pin "4") (pinfunction "DQ_4") (pintype "bidirectional"))
      (node (ref "U$48") (pin "4") (pinfunction "DQ_4") (pintype "bidirectional"))
      (node (ref "U1") (pin "76") (pinfunction "(AD2)PA2_76") (pintype "bidirectional"))
    )
    (net (code "144") (name "TX") (class "Default")
      (node (ref "Q3") (pin "3") (pinfunction "D_3") (pintype "passive"))
      (node (ref "R22") (pin "1") (pinfunction "1_1") (pintype "passive"))
      (node (ref "U1") (pin "46") (pinfunction "(TXD1/INT3)PD3_46") (pintype "bidirectional"))
    )
    (net (code "145") (name "TX0") (class "Default")
      (node (ref "U$50") (pin "9") (pinfunction "9_9") (pintype "bidirectional"))
      (node (ref "U1") (pin "3") (pinfunction "(TXD0)PE1_3") (pintype "bidirectional"))
    )
    (net (code "146") (name "VCC-ISO") (class "Default")
      (node (ref "C20") (pin "1") (pinfunction "1_1") (pintype "passive"))
      (node (ref "C21") (pin "1") (pinfunction "1_1") (pintype "passive"))
      (node (ref "C32") (pin "1") (pinfunction "1_1") (pintype "passive"))
      (node (ref "C46") (pin "1") (pinfunction "1_1") (pintype "passive"))
      (node (ref "C47") (pin "1") (pinfunction "1_1") (pintype "passive"))
      (node (ref "C48") (pin "2") (pinfunction "2_2") (pintype "passive"))
      (node (ref "C49") (pin "1") (pinfunction "1_1") (pintype "passive"))
      (node (ref "C59") (pin "2") (pinfunction "2_2") (pintype "passive"))
      (node (ref "C67") (pin "1") (pinfunction "1_1") (pintype "passive"))
      (node (ref "L3") (pin "2") (pinfunction "2_2") (pintype "passive"))
      (node (ref "R57") (pin "1") (pinfunction "1_1") (pintype "passive"))
      (node (ref "R58") (pin "1") (pinfunction "1_1") (pintype "passive"))
      (node (ref "U$11") (pin "11") (pinfunction "VBRIDGE_B_11") (pintype "bidirectional"))
      (node (ref "U$11") (pin "4") (pinfunction "VBRIDGE_A_4") (pintype "bidirectional"))
      (node (ref "U$12") (pin "P$7") (pinfunction "VBRIDGE_P$7") (pintype "bidirectional"))
      (node (ref "U$22") (pin "2") (pinfunction "VIN_2") (pintype "bidirectional"))
      (node (ref "U$7") (pin "1") (pinfunction "DVDD_1") (pintype "bidirectional"))
      (node (ref "U$7") (pin "22") (pinfunction "AVDD_22") (pintype "bidirectional"))
    )
    (net (code "147") (name "VCC_GPS") (class "Default")
      (node (ref "C4") (pin "2") (pinfunction "2_2") (pintype "passive"))
      (node (ref "C73") (pin "1") (pinfunction "1_1") (pintype "passive"))
      (node (ref "C74") (pin "1") (pinfunction "1_1") (pintype "passive"))
      (node (ref "C75") (pin "1") (pinfunction "1_1") (pintype "passive"))
      (node (ref "L1") (pin "2") (pinfunction "2_2") (pintype "passive"))
      (node (ref "R10") (pin "2") (pinfunction "2_2") (pintype "passive"))
      (node (ref "R14") (pin "2") (pinfunction "2_2") (pintype "passive"))
      (node (ref "T1") (pin "1") (pinfunction "D_1") (pintype "passive"))
      (node (ref "T1") (pin "2") (pinfunction "D_2") (pintype "passive"))
      (node (ref "T1") (pin "5") (pinfunction "D_5") (pintype "passive"))
      (node (ref "T1") (pin "6") (pinfunction "D_6") (pintype "passive"))
      (node (ref "U3") (pin "2") (pinfunction "VCC_2") (pintype "bidirectional"))
      (node (ref "U3") (pin "36") (pinfunction "REGEN_36") (pintype "bidirectional"))
      (node (ref "U3") (pin "58") (pinfunction "VCC_58") (pintype "bidirectional"))
    )
    (net (code "148") (name "VIN_3.3") (class "Default")
      (node (ref "C26") (pin "1") (pinfunction "1_1") (pintype "passive"))
      (node (ref "C27") (pin "1") (pinfunction "1_1") (pintype "passive"))
      (node (ref "C28") (pin "A") (pinfunction "+_A") (pintype "passive"))
      (node (ref "L4") (pin "1") (pinfunction "1_1") (pintype "passive"))
      (node (ref "R30") (pin "2") (pinfunction "2_2") (pintype "passive"))
      (node (ref "R36") (pin "1") (pinfunction "1_1") (pintype "passive"))
      (node (ref "U5") (pin "5") (pinfunction "VIN_5") (pintype "power_in"))
      (node (ref "U5") (pin "6") (pinfunction "EN_6") (pintype "input"))
      (node (ref "U5") (pin "8") (pinfunction "PS_8") (pintype "input"))
    )
    (net (code "149") (name "VIN_5.0") (class "Default")
      (node (ref "C29") (pin "A") (pinfunction "+_A") (pintype "passive"))
      (node (ref "C57") (pin "1") (pinfunction "1_1") (pintype "passive"))
      (node (ref "C58") (pin "1") (pinfunction "1_1") (pintype "passive"))
      (node (ref "L8") (pin "1") (pinfunction "1_1") (pintype "passive"))
      (node (ref "R25") (pin "1") (pinfunction "1_1") (pintype "passive"))
      (node (ref "U11") (pin "5") (pinfunction "VIN_5") (pintype "power_in"))
      (node (ref "U11") (pin "7") (pinfunction "UVLO_7") (pintype "passive"))
      (node (ref "U11") (pin "8") (pinfunction "PS_8") (pintype "input"))
    )
    (net (code "150") (name "XN") (class "Default")
      (node (ref "C64") (pin "1") (pinfunction "1_1") (pintype "passive"))
      (node (ref "C71") (pin "2") (pinfunction "2_2") (pintype "passive"))
      (node (ref "R49") (pin "1") (pinfunction "1_1") (pintype "passive"))
      (node (ref "U$7") (pin "11") (pinfunction "AIN0_11") (pintype "bidirectional"))
    )
    (net (code "151") (name "XP") (class "Default")
      (node (ref "C63") (pin "1") (pinfunction "1_1") (pintype "passive"))
      (node (ref "C71") (pin "1") (pinfunction "1_1") (pintype "passive"))
      (node (ref "R48") (pin "1") (pinfunction "1_1") (pintype "passive"))
      (node (ref "U$7") (pin "12") (pinfunction "AIN1_12") (pintype "bidirectional"))
    )
    (net (code "152") (name "X_OUT+") (class "Default")
      (node (ref "R48") (pin "2") (pinfunction "2_2") (pintype "passive"))
      (node (ref "U$11") (pin "2") (pinfunction "OUT+A_2") (pintype "bidirectional"))
    )
    (net (code "153") (name "X_OUT-") (class "Default")
      (node (ref "R49") (pin "2") (pinfunction "2_2") (pintype "passive"))
      (node (ref "U$11") (pin "5") (pinfunction "OUT-A_5") (pintype "bidirectional"))
    )
    (net (code "154") (name "YN") (class "Default")
      (node (ref "C66") (pin "1") (pinfunction "1_1") (pintype "passive"))
      (node (ref "C72") (pin "2") (pinfunction "2_2") (pintype "passive"))
      (node (ref "R51") (pin "1") (pinfunction "1_1") (pintype "passive"))
      (node (ref "U$7") (pin "14") (pinfunction "AIN5_14") (pintype "bidirectional"))
    )
    (net (code "155") (name "YP") (class "Default")
      (node (ref "C65") (pin "1") (pinfunction "1_1") (pintype "passive"))
      (node (ref "C72") (pin "1") (pinfunction "1_1") (pintype "passive"))
      (node (ref "R50") (pin "1") (pinfunction "1_1") (pintype "passive"))
      (node (ref "U$7") (pin "13") (pinfunction "AIN4_13") (pintype "bidirectional"))
    )
    (net (code "156") (name "Y_OUT+") (class "Default")
      (node (ref "R50") (pin "2") (pinfunction "2_2") (pintype "passive"))
      (node (ref "U$11") (pin "9") (pinfunction "OUT+B_9") (pintype "bidirectional"))
    )
    (net (code "157") (name "Y_OUT-") (class "Default")
      (node (ref "R51") (pin "2") (pinfunction "2_2") (pintype "passive"))
      (node (ref "U$11") (pin "12") (pinfunction "OUT-B_12") (pintype "bidirectional"))
    )
    (net (code "158") (name "ZN") (class "Default")
      (node (ref "C62") (pin "1") (pinfunction "1_1") (pintype "passive"))
      (node (ref "C70") (pin "2") (pinfunction "2_2") (pintype "passive"))
      (node (ref "R47") (pin "1") (pinfunction "1_1") (pintype "passive"))
      (node (ref "U$7") (pin "17") (pinfunction "AIN2_17") (pintype "bidirectional"))
    )
    (net (code "159") (name "ZP") (class "Default")
      (node (ref "C61") (pin "1") (pinfunction "1_1") (pintype "passive"))
      (node (ref "C70") (pin "1") (pinfunction "1_1") (pintype "passive"))
      (node (ref "R46") (pin "1") (pinfunction "1_1") (pintype "passive"))
      (node (ref "U$7") (pin "18") (pinfunction "AIN3_18") (pintype "bidirectional"))
    )
    (net (code "160") (name "Z_OUT+") (class "Default")
      (node (ref "R46") (pin "2") (pinfunction "2_2") (pintype "passive"))
      (node (ref "U$12") (pin "P$5") (pinfunction "OUT+_P$5") (pintype "bidirectional"))
    )
    (net (code "161") (name "Z_OUT-") (class "Default")
      (node (ref "R47") (pin "2") (pinfunction "2_2") (pintype "passive"))
      (node (ref "U$12") (pin "P$8") (pinfunction "OUT-_P$8") (pintype "bidirectional"))
    )
    (net (code "162") (name "unconnected-(JP5-PadD+)") (class "Default")
      (node (ref "JP5") (pin "D+") (pinfunction "D+_D+") (pintype "bidirectional"))
    )
    (net (code "163") (name "unconnected-(JP5-PadD-)") (class "Default")
      (node (ref "JP5") (pin "D-") (pinfunction "D-_D-") (pintype "bidirectional"))
    )
    (net (code "164") (name "unconnected-(S1-PadNO)") (class "Default")
      (node (ref "S1") (pin "NO") (pinfunction "NO_NO") (pintype "passive"))
    )
    (net (code "165") (name "unconnected-(S2-PadNO)") (class "Default")
      (node (ref "S2") (pin "NO") (pinfunction "NO_NO") (pintype "passive"))
    )
    (net (code "166") (name "unconnected-(S3-PadNO)") (class "Default")
      (node (ref "S3") (pin "NO") (pinfunction "NO_NO") (pintype "passive"))
    )
    (net (code "167") (name "unconnected-(S4-PadNO)") (class "Default")
      (node (ref "S4") (pin "NO") (pinfunction "NO_NO") (pintype "passive"))
    )
    (net (code "168") (name "unconnected-(U$1-6A-Pad14)") (class "Default")
      (node (ref "U$1") (pin "14") (pinfunction "6A_14") (pintype "bidirectional"))
    )
    (net (code "169") (name "unconnected-(U$1-6Y-Pad15)") (class "Default")
      (node (ref "U$1") (pin "15") (pinfunction "6Y_15") (pintype "bidirectional"))
    )
    (net (code "170") (name "unconnected-(U$3-GPIO2-Pad8)") (class "Default")
      (node (ref "U$3") (pin "8") (pinfunction "GPIO2_8") (pintype "bidirectional"))
    )
    (net (code "171") (name "unconnected-(U$7-AIN6-Pad15)") (class "Default")
      (node (ref "U$7") (pin "15") (pinfunction "AIN6_15") (pintype "bidirectional"))
    )
    (net (code "172") (name "unconnected-(U$7-AIN7-Pad16)") (class "Default")
      (node (ref "U$7") (pin "16") (pinfunction "AIN7_16") (pintype "bidirectional"))
    )
    (net (code "173") (name "unconnected-(U$7-IEXC1-Pad20)") (class "Default")
      (node (ref "U$7") (pin "20") (pinfunction "IEXC1_20") (pintype "bidirectional"))
    )
    (net (code "174") (name "unconnected-(U$7-IEXC2-Pad19)") (class "Default")
      (node (ref "U$7") (pin "19") (pinfunction "IEXC2_19") (pintype "bidirectional"))
    )
    (net (code "175") (name "unconnected-(U$7-REFP1-Pad7)") (class "Default")
      (node (ref "U$7") (pin "7") (pinfunction "REFP1_7") (pintype "bidirectional"))
    )
    (net (code "176") (name "unconnected-(U$11-OFFSET+A-Pad17)") (class "Default")
      (node (ref "U$11") (pin "17") (pinfunction "OFFSET+A_17") (pintype "bidirectional"))
    )
    (net (code "177") (name "unconnected-(U$11-OFFSET+B-Pad15)") (class "Default")
      (node (ref "U$11") (pin "15") (pinfunction "OFFSET+B_15") (pintype "bidirectional"))
    )
    (net (code "178") (name "unconnected-(U$22-NC-Pad3)") (class "Default")
      (node (ref "U$22") (pin "3") (pinfunction "NC_3") (pintype "bidirectional"))
    )
    (net (code "179") (name "unconnected-(U$22-NC-Pad7)") (class "Default")
      (node (ref "U$22") (pin "7") (pinfunction "NC_7") (pintype "bidirectional"))
    )
    (net (code "180") (name "unconnected-(U$22-TP-Pad1)") (class "Default")
      (node (ref "U$22") (pin "1") (pinfunction "TP_1") (pintype "bidirectional"))
    )
    (net (code "181") (name "unconnected-(U$22-TP-Pad8)") (class "Default")
      (node (ref "U$22") (pin "8") (pinfunction "TP_8") (pintype "bidirectional"))
    )
    (net (code "182") (name "unconnected-(U$22-TRIM-Pad5)") (class "Default")
      (node (ref "U$22") (pin "5") (pinfunction "TRIM_5") (pintype "bidirectional"))
    )
    (net (code "183") (name "unconnected-(U$50-Pad2)") (class "Default")
      (node (ref "U$50") (pin "2") (pinfunction "2_2") (pintype "bidirectional"))
    )
    (net (code "184") (name "unconnected-(U$50-Pad8)") (class "Default")
      (node (ref "U$50") (pin "8") (pinfunction "8_8") (pintype "bidirectional"))
    )
    (net (code "185") (name "unconnected-(U1-(A8)PC0-Pad53)") (class "Default")
      (node (ref "U1") (pin "53") (pinfunction "(A8)PC0_53") (pintype "bidirectional"))
    )
    (net (code "186") (name "unconnected-(U1-(A9)PC1-Pad54)") (class "Default")
      (node (ref "U1") (pin "54") (pinfunction "(A9)PC1_54") (pintype "bidirectional"))
    )
    (net (code "187") (name "unconnected-(U1-(A10)PC2-Pad55)") (class "Default")
      (node (ref "U1") (pin "55") (pinfunction "(A10)PC2_55") (pintype "bidirectional"))
    )
    (net (code "188") (name "unconnected-(U1-(A11)PC3-Pad56)") (class "Default")
      (node (ref "U1") (pin "56") (pinfunction "(A11)PC3_56") (pintype "bidirectional"))
    )
    (net (code "189") (name "unconnected-(U1-(A12)PC4-Pad57)") (class "Default")
      (node (ref "U1") (pin "57") (pinfunction "(A12)PC4_57") (pintype "bidirectional"))
    )
    (net (code "190") (name "unconnected-(U1-(A13)PC5-Pad58)") (class "Default")
      (node (ref "U1") (pin "58") (pinfunction "(A13)PC5_58") (pintype "bidirectional"))
    )
    (net (code "191") (name "unconnected-(U1-(A14)PC6-Pad59)") (class "Default")
      (node (ref "U1") (pin "59") (pinfunction "(A14)PC6_59") (pintype "bidirectional"))
    )
    (net (code "192") (name "unconnected-(U1-(A15)PC7-Pad60)") (class "Default")
      (node (ref "U1") (pin "60") (pinfunction "(A15)PC7_60") (pintype "bidirectional"))
    )
    (net (code "193") (name "unconnected-(U1-(AD0)PA0-Pad78)") (class "Default")
      (node (ref "U1") (pin "78") (pinfunction "(AD0)PA0_78") (pintype "bidirectional"))
    )
    (net (code "194") (name "unconnected-(U1-(AD5)PA5-Pad73)") (class "Default")
      (node (ref "U1") (pin "73") (pinfunction "(AD5)PA5_73") (pintype "bidirectional"))
    )
    (net (code "195") (name "unconnected-(U1-(AD6)PA6-Pad72)") (class "Default")
      (node (ref "U1") (pin "72") (pinfunction "(AD6)PA6_72") (pintype "bidirectional"))
    )
    (net (code "196") (name "unconnected-(U1-(AD7)PA7-Pad71)") (class "Default")
      (node (ref "U1") (pin "71") (pinfunction "(AD7)PA7_71") (pintype "bidirectional"))
    )
    (net (code "197") (name "unconnected-(U1-(ADC1)PF1-Pad96)") (class "Default")
      (node (ref "U1") (pin "96") (pinfunction "(ADC1)PF1_96") (pintype "bidirectional"))
    )
    (net (code "198") (name "unconnected-(U1-(ADC2)PF2-Pad95)") (class "Default")
      (node (ref "U1") (pin "95") (pinfunction "(ADC2)PF2_95") (pintype "bidirectional"))
    )
    (net (code "199") (name "unconnected-(U1-(ADC3)PF3-Pad94)") (class "Default")
      (node (ref "U1") (pin "94") (pinfunction "(ADC3)PF3_94") (pintype "bidirectional"))
    )
    (net (code "200") (name "unconnected-(U1-(ADC4{slash}TCK)PF4-Pad93)") (class "Default")
      (node (ref "U1") (pin "93") (pinfunction "(ADC4/TCK)PF4_93") (pintype "bidirectional"))
    )
    (net (code "201") (name "unconnected-(U1-(ADC5{slash}TMS)PF5-Pad92)") (class "Default")
      (node (ref "U1") (pin "92") (pinfunction "(ADC5/TMS)PF5_92") (pintype "bidirectional"))
    )
    (net (code "202") (name "unconnected-(U1-(ADC6{slash}TDO)PF6-Pad91)") (class "Default")
      (node (ref "U1") (pin "91") (pinfunction "(ADC6/TDO)PF6_91") (pintype "bidirectional"))
    )
    (net (code "203") (name "unconnected-(U1-(ADC7{slash}TDI)PF7-Pad90)") (class "Default")
      (node (ref "U1") (pin "90") (pinfunction "(ADC7/TDI)PF7_90") (pintype "bidirectional"))
    )
    (net (code "204") (name "unconnected-(U1-(ALE)PG2-Pad70)") (class "Default")
      (node (ref "U1") (pin "70") (pinfunction "(ALE)PG2_70") (pintype "bidirectional"))
    )
    (net (code "205") (name "unconnected-(U1-(CLKO{slash}ICP3{slash}INT7)PE7-Pad9)") (class "Default")
      (node (ref "U1") (pin "9") (pinfunction "(CLKO/ICP3/INT7)PE7_9") (pintype "bidirectional"))
    )
    (net (code "206") (name "unconnected-(U1-(ICP1)PD4-Pad47)") (class "Default")
      (node (ref "U1") (pin "47") (pinfunction "(ICP1)PD4_47") (pintype "bidirectional"))
    )
    (net (code "207") (name "unconnected-(U1-(RD)PG1-Pad52)") (class "Default")
      (node (ref "U1") (pin "52") (pinfunction "(RD)PG1_52") (pintype "bidirectional"))
    )
    (net (code "208") (name "unconnected-(U1-(T0)PD7-Pad50)") (class "Default")
      (node (ref "U1") (pin "50") (pinfunction "(T0)PD7_50") (pintype "bidirectional"))
    )
    (net (code "209") (name "unconnected-(U1-(T1)PD6-Pad49)") (class "Default")
      (node (ref "U1") (pin "49") (pinfunction "(T1)PD6_49") (pintype "bidirectional"))
    )
    (net (code "210") (name "unconnected-(U1-(T3{slash}INT6)PE6-Pad8)") (class "Default")
      (node (ref "U1") (pin "8") (pinfunction "(T3/INT6)PE6_8") (pintype "bidirectional"))
    )
    (net (code "211") (name "unconnected-(U1-(XCK0{slash}AIN0)PE2-Pad4)") (class "Default")
      (node (ref "U1") (pin "4") (pinfunction "(XCK0/AIN0)PE2_4") (pintype "bidirectional"))
    )
    (net (code "212") (name "unconnected-(U1-(XCK1)PD5-Pad48)") (class "Default")
      (node (ref "U1") (pin "48") (pinfunction "(XCK1)PD5_48") (pintype "bidirectional"))
    )
    (net (code "213") (name "unconnected-(U1-PH2(XCK2)-Pad14)") (class "Default")
      (node (ref "U1") (pin "14") (pinfunction "PH2(XCK2)_14") (pintype "bidirectional"))
    )
    (net (code "214") (name "unconnected-(U1-PJ0(RXD3{slash}PCINT9)-Pad63)") (class "Default")
      (node (ref "U1") (pin "63") (pinfunction "PJ0(RXD3/PCINT9)_63") (pintype "bidirectional"))
    )
    (net (code "215") (name "unconnected-(U1-PJ1(TXD3{slash}PCINT10)-Pad64)") (class "Default")
      (node (ref "U1") (pin "64") (pinfunction "PJ1(TXD3/PCINT10)_64") (pintype "bidirectional"))
    )
    (net (code "216") (name "unconnected-(U1-PJ2(XCK3{slash}PCINT11)-Pad65)") (class "Default")
      (node (ref "U1") (pin "65") (pinfunction "PJ2(XCK3/PCINT11)_65") (pintype "bidirectional"))
    )
    (net (code "217") (name "unconnected-(U1-PJ3(PCINT12)-Pad66)") (class "Default")
      (node (ref "U1") (pin "66") (pinfunction "PJ3(PCINT12)_66") (pintype "bidirectional"))
    )
    (net (code "218") (name "unconnected-(U1-PJ4(PCINT13)-Pad67)") (class "Default")
      (node (ref "U1") (pin "67") (pinfunction "PJ4(PCINT13)_67") (pintype "bidirectional"))
    )
    (net (code "219") (name "unconnected-(U1-PJ5(PCINT14)-Pad68)") (class "Default")
      (node (ref "U1") (pin "68") (pinfunction "PJ5(PCINT14)_68") (pintype "bidirectional"))
    )
    (net (code "220") (name "unconnected-(U1-PJ6(PCINT15)-Pad69)") (class "Default")
      (node (ref "U1") (pin "69") (pinfunction "PJ6(PCINT15)_69") (pintype "bidirectional"))
    )
    (net (code "221") (name "unconnected-(U1-PJ7-Pad79)") (class "Default")
      (node (ref "U1") (pin "79") (pinfunction "PJ7_79") (pintype "bidirectional"))
    )
    (net (code "222") (name "unconnected-(U1-PK0(ADC8{slash}PCINT16)-Pad89)") (class "Default")
      (node (ref "U1") (pin "89") (pinfunction "PK0(ADC8/PCINT16)_89") (pintype "bidirectional"))
    )
    (net (code "223") (name "unconnected-(U1-PK1(ADC9{slash}PCINT17)-Pad88)") (class "Default")
      (node (ref "U1") (pin "88") (pinfunction "PK1(ADC9/PCINT17)_88") (pintype "bidirectional"))
    )
    (net (code "224") (name "unconnected-(U1-PK6(ADC14{slash}PCINT22)-Pad83)") (class "Default")
      (node (ref "U1") (pin "83") (pinfunction "PK6(ADC14/PCINT22)_83") (pintype "bidirectional"))
    )
    (net (code "225") (name "unconnected-(U1-PK7(ADC15{slash}PCINT23)-Pad82)") (class "Default")
      (node (ref "U1") (pin "82") (pinfunction "PK7(ADC15/PCINT23)_82") (pintype "bidirectional"))
    )
    (net (code "226") (name "unconnected-(U1-PL0(ICP4)-Pad35)") (class "Default")
      (node (ref "U1") (pin "35") (pinfunction "PL0(ICP4)_35") (pintype "bidirectional"))
    )
    (net (code "227") (name "unconnected-(U1-PL1(ICP5)-Pad36)") (class "Default")
      (node (ref "U1") (pin "36") (pinfunction "PL1(ICP5)_36") (pintype "bidirectional"))
    )
    (net (code "228") (name "unconnected-(U1-PL2(T5)-Pad37)") (class "Default")
      (node (ref "U1") (pin "37") (pinfunction "PL2(T5)_37") (pintype "bidirectional"))
    )
    (net (code "229") (name "unconnected-(U1-PL3(OC5A)-Pad38)") (class "Default")
      (node (ref "U1") (pin "38") (pinfunction "PL3(OC5A)_38") (pintype "bidirectional"))
    )
    (net (code "230") (name "unconnected-(U1-PL4(OC5B)-Pad39)") (class "Default")
      (node (ref "U1") (pin "39") (pinfunction "PL4(OC5B)_39") (pintype "bidirectional"))
    )
    (net (code "231") (name "unconnected-(U1-PL5(OC5C)-Pad40)") (class "Default")
      (node (ref "U1") (pin "40") (pinfunction "PL5(OC5C)_40") (pintype "bidirectional"))
    )
    (net (code "232") (name "unconnected-(U1-PL6-Pad41)") (class "Default")
      (node (ref "U1") (pin "41") (pinfunction "PL6_41") (pintype "bidirectional"))
    )
    (net (code "233") (name "unconnected-(U1-PL7-Pad42)") (class "Default")
      (node (ref "U1") (pin "42") (pinfunction "PL7_42") (pintype "bidirectional"))
    )
    (net (code "234") (name "unconnected-(U2-NC-PadRSV1)") (class "Default")
      (node (ref "U2") (pin "RSV1") (pinfunction "NC_RSV1") (pintype "bidirectional"))
    )
    (net (code "235") (name "unconnected-(U2-RSV-PadRSV2)") (class "Default")
      (node (ref "U2") (pin "RSV2") (pinfunction "RSV_RSV2") (pintype "bidirectional"))
    )
    (net (code "236") (name "unconnected-(U3-CLK-Pad41)") (class "Default")
      (node (ref "U3") (pin "41") (pinfunction "CLK_41") (pintype "bidirectional"))
    )
    (net (code "237") (name "unconnected-(U3-CSN-Pad43)") (class "Default")
      (node (ref "U3") (pin "43") (pinfunction "CSN_43") (pintype "bidirectional"))
    )
    (net (code "238") (name "unconnected-(U3-GPIO1-Pad6)") (class "Default")
      (node (ref "U3") (pin "6") (pinfunction "GPIO1_6") (pintype "bidirectional"))
    )
    (net (code "239") (name "unconnected-(U3-GPIO2-Pad5)") (class "Default")
      (node (ref "U3") (pin "5") (pinfunction "GPIO2_5") (pintype "bidirectional"))
    )
    (net (code "240") (name "unconnected-(U3-GPIO3-Pad48)") (class "Default")
      (node (ref "U3") (pin "48") (pinfunction "GPIO3_48") (pintype "bidirectional"))
    )
    (net (code "241") (name "unconnected-(U3-GPIO4-Pad47)") (class "Default")
      (node (ref "U3") (pin "47") (pinfunction "GPIO4_47") (pintype "bidirectional"))
    )
    (net (code "242") (name "unconnected-(U3-GPIO6-Pad63)") (class "Default")
      (node (ref "U3") (pin "63") (pinfunction "GPIO6_63") (pintype "bidirectional"))
    )
    (net (code "243") (name "unconnected-(U3-GPIO20-Pad14)") (class "Default")
      (node (ref "U3") (pin "14") (pinfunction "GPIO20_14") (pintype "bidirectional"))
    )
    (net (code "244") (name "unconnected-(U3-GPIO22-Pad12)") (class "Default")
      (node (ref "U3") (pin "12") (pinfunction "GPIO22_12") (pintype "bidirectional"))
    )
    (net (code "245") (name "unconnected-(U3-GPIO23-Pad13)") (class "Default")
      (node (ref "U3") (pin "13") (pinfunction "GPIO23_13") (pintype "bidirectional"))
    )
    (net (code "246") (name "unconnected-(U3-GPIO24-Pad8)") (class "Default")
      (node (ref "U3") (pin "8") (pinfunction "GPIO24_8") (pintype "bidirectional"))
    )
    (net (code "247") (name "unconnected-(U3-GPIO25-Pad53)") (class "Default")
      (node (ref "U3") (pin "53") (pinfunction "GPIO25_53") (pintype "bidirectional"))
    )
    (net (code "248") (name "unconnected-(U3-GPIO28-Pad59)") (class "Default")
      (node (ref "U3") (pin "59") (pinfunction "GPIO28_59") (pintype "bidirectional"))
    )
    (net (code "249") (name "unconnected-(U3-GPIO29-Pad16)") (class "Default")
      (node (ref "U3") (pin "16") (pinfunction "GPIO29_16") (pintype "bidirectional"))
    )
    (net (code "250") (name "unconnected-(U3-GPIO30-Pad54)") (class "Default")
      (node (ref "U3") (pin "54") (pinfunction "GPIO30_54") (pintype "bidirectional"))
    )
    (net (code "251") (name "unconnected-(U3-MISO-Pad39)") (class "Default")
      (node (ref "U3") (pin "39") (pinfunction "MISO_39") (pintype "bidirectional"))
    )
    (net (code "252") (name "unconnected-(U3-MOSI-Pad38)") (class "Default")
      (node (ref "U3") (pin "38") (pinfunction "MOSI_38") (pintype "bidirectional"))
    )
    (net (code "253") (name "unconnected-(U3-PIO5-Pad50)") (class "Default")
      (node (ref "U3") (pin "50") (pinfunction "PIO5_50") (pintype "bidirectional"))
    )
    (net (code "254") (name "unconnected-(U3-PIO11-Pad51)") (class "Default")
      (node (ref "U3") (pin "51") (pinfunction "PIO11_51") (pintype "bidirectional"))
    )
    (net (code "255") (name "unconnected-(U3-PIO12-Pad4)") (class "Default")
      (node (ref "U3") (pin "4") (pinfunction "PIO12_4") (pintype "bidirectional"))
    )
    (net (code "256") (name "unconnected-(U3-PIO14-Pad37)") (class "Default")
      (node (ref "U3") (pin "37") (pinfunction "PIO14_37") (pintype "bidirectional"))
    )
    (net (code "257") (name "unconnected-(U3-PIO15-Pad55)") (class "Default")
      (node (ref "U3") (pin "55") (pinfunction "PIO15_55") (pintype "bidirectional"))
    )
    (net (code "258") (name "unconnected-(U3-PPS-Pad40)") (class "Default")
      (node (ref "U3") (pin "40") (pinfunction "PPS_40") (pintype "bidirectional"))
    )
    (net (code "259") (name "unconnected-(U3-RTC-Pad17)") (class "Default")
      (node (ref "U3") (pin "17") (pinfunction "RTC_17") (pintype "bidirectional"))
    )
    (net (code "260") (name "unconnected-(U3-RXD1-Pad52)") (class "Default")
      (node (ref "U3") (pin "52") (pinfunction "RXD1_52") (pintype "bidirectional"))
    )
    (net (code "261") (name "unconnected-(U3-SCL-Pad46)") (class "Default")
      (node (ref "U3") (pin "46") (pinfunction "SCL_46") (pintype "bidirectional"))
    )
    (net (code "262") (name "unconnected-(U3-SDA-Pad45)") (class "Default")
      (node (ref "U3") (pin "45") (pinfunction "SDA_45") (pintype "bidirectional"))
    )
    (net (code "263") (name "unconnected-(U3-TXD1-Pad57)") (class "Default")
      (node (ref "U3") (pin "57") (pinfunction "TXD1_57") (pintype "bidirectional"))
    )
    (net (code "264") (name "unconnected-(U6-DEN(G)-Pad10)") (class "Default")
      (node (ref "U6") (pin "10") (pinfunction "DEN(G)_10") (pintype "bidirectional"))
    )
    (net (code "265") (name "unconnected-(U6-DRDY(G)-Pad12)") (class "Default")
      (node (ref "U6") (pin "12") (pinfunction "DRDY(G)_12") (pintype "bidirectional"))
    )
    (net (code "266") (name "unconnected-(U6-INT(G)-Pad11)") (class "Default")
      (node (ref "U6") (pin "11") (pinfunction "INT(G)_11") (pintype "bidirectional"))
    )
    (net (code "267") (name "unconnected-(U6-INT1(XM)-Pad13)") (class "Default")
      (node (ref "U6") (pin "13") (pinfunction "INT1(XM)_13") (pintype "bidirectional"))
    )
    (net (code "268") (name "unconnected-(U6-INT2(XM)-Pad14)") (class "Default")
      (node (ref "U6") (pin "14") (pinfunction "INT2(XM)_14") (pintype "bidirectional"))
    )
    (net (code "269") (name "unconnected-(U7-INT-Pad5)") (class "Default")
      (node (ref "U7") (pin "5") (pinfunction "INT_5") (pintype "output"))
    )
    (net (code "270") (name "unconnected-(U9-INT-Pad5)") (class "Default")
      (node (ref "U9") (pin "5") (pinfunction "INT_5") (pintype "output"))
    )
  )
)
